# Sheet1.net
KiCad netlist of a schematic drawn in Altium Designer
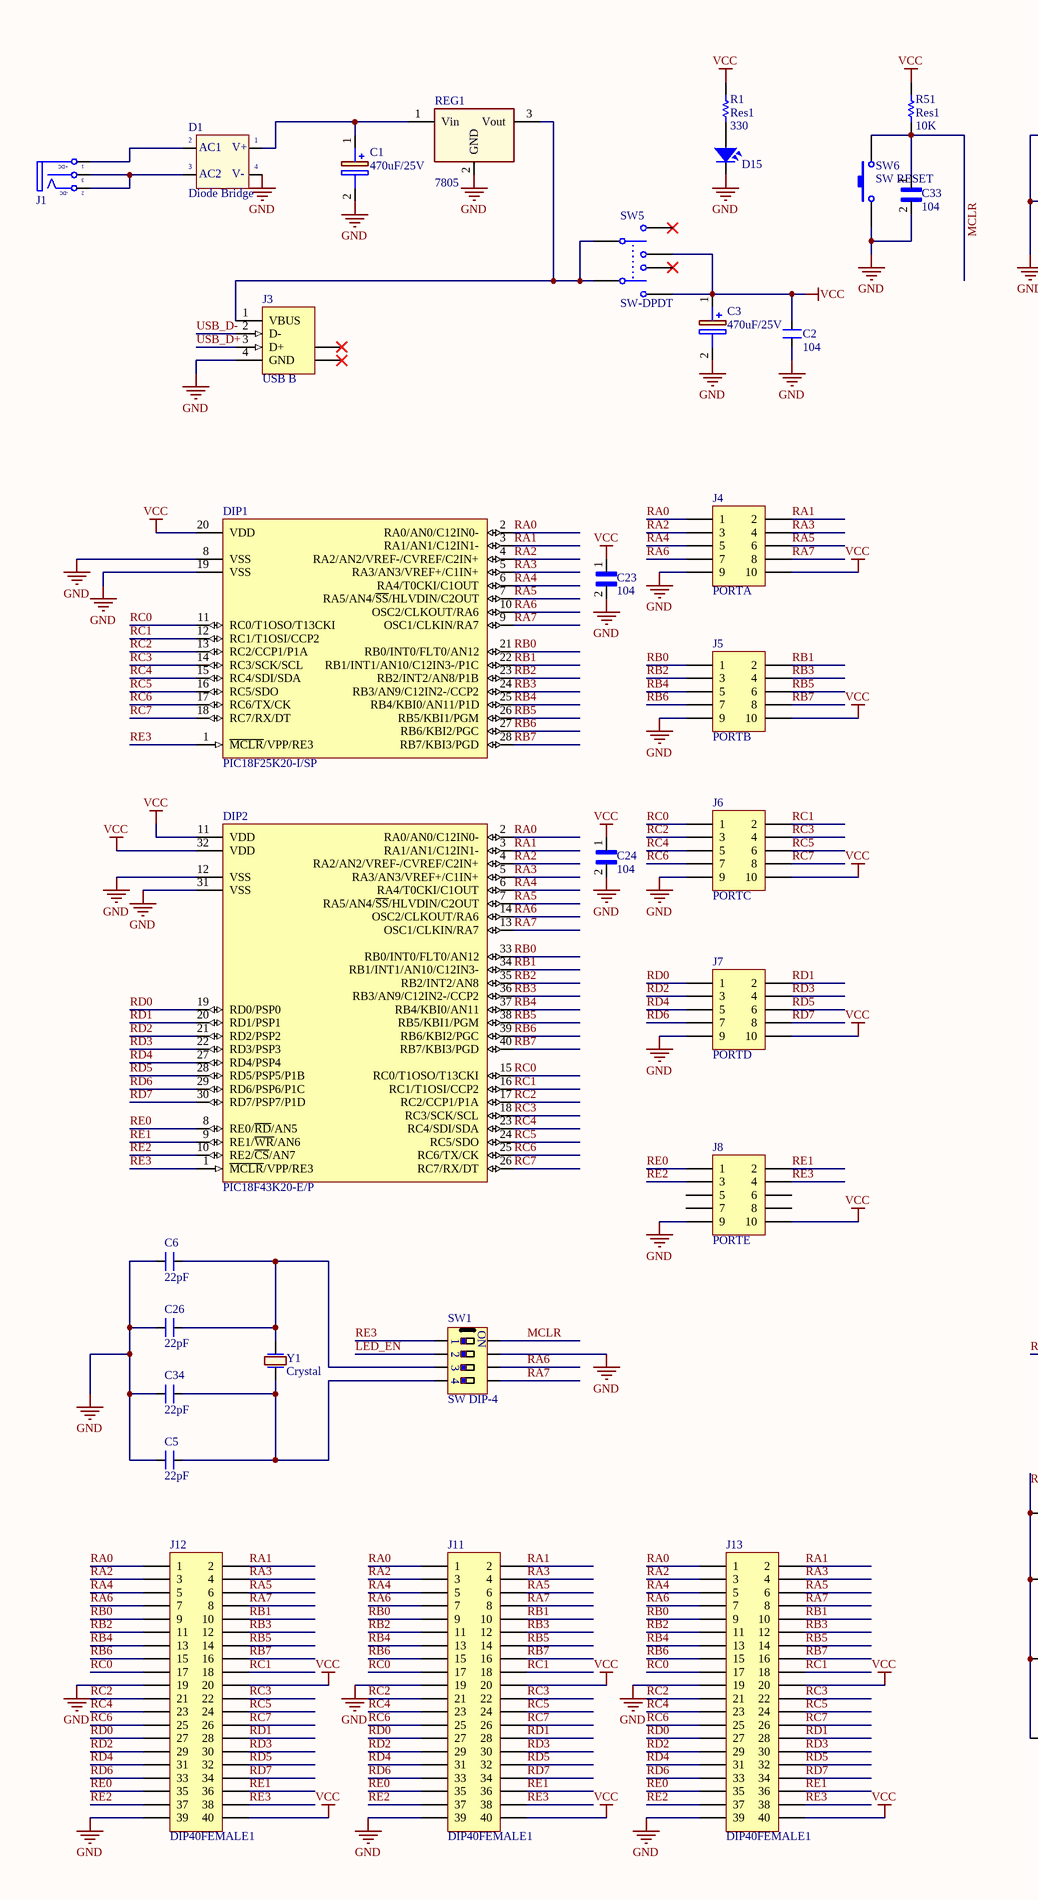
[diagram p0: Sheet1.SchDoc, left]
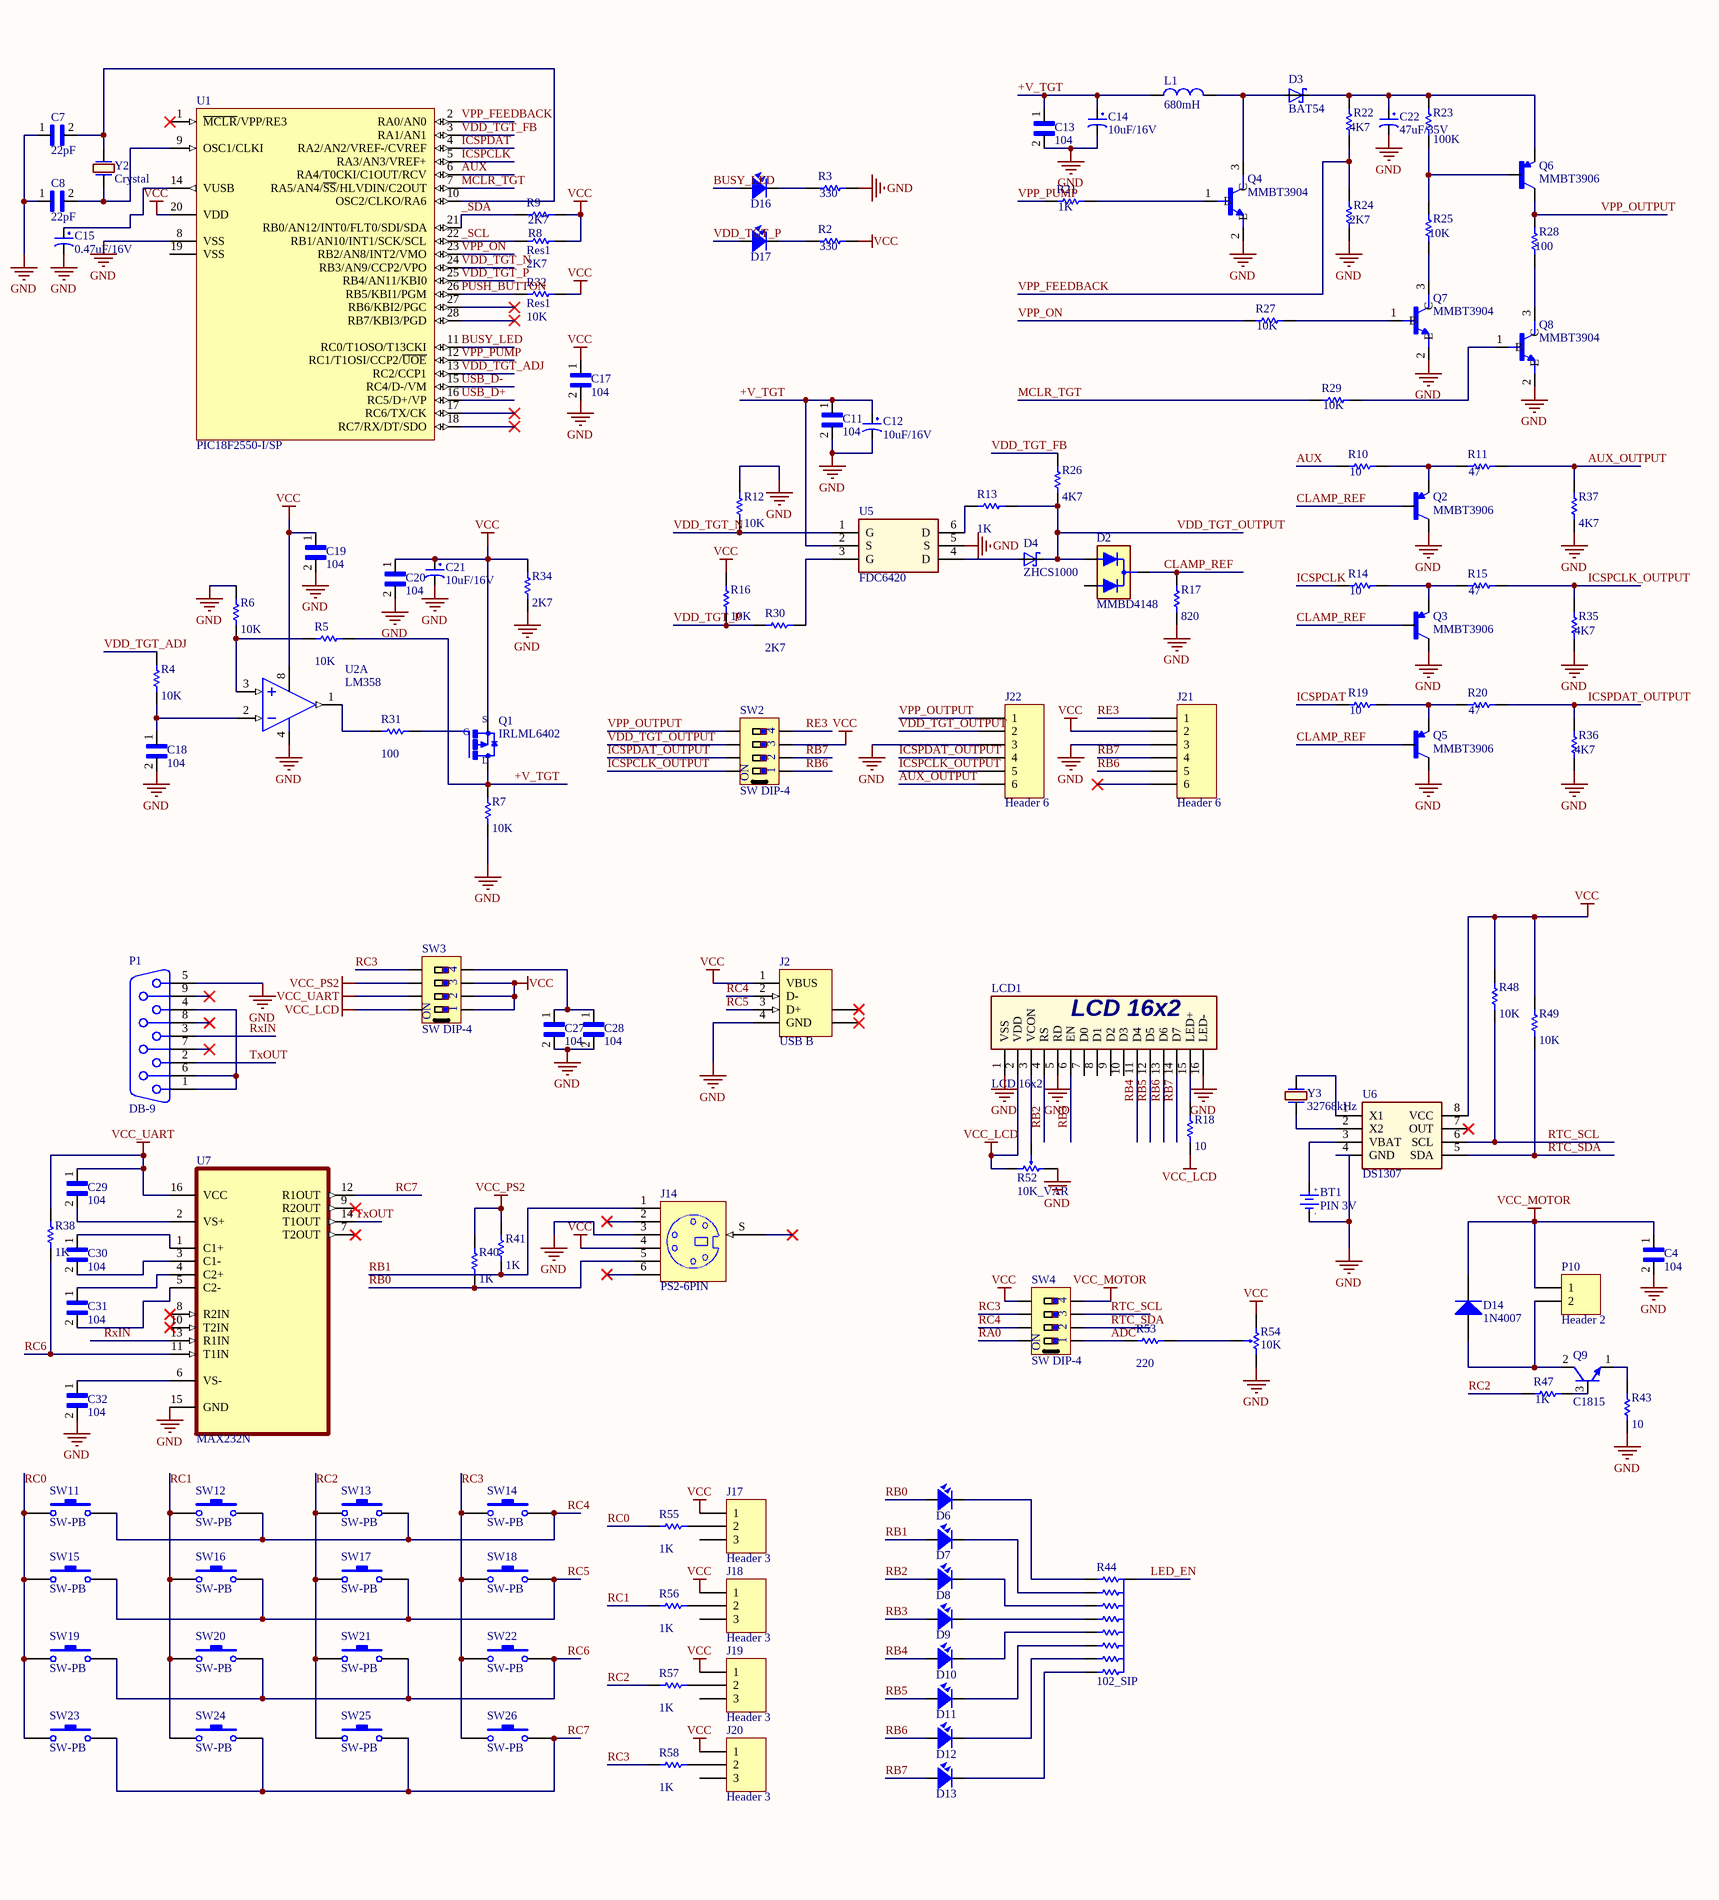
[diagram p1: Sheet1.SchDoc, right]

(export (version "E")
  (design (tool "Eeschema 10.0.6"))
  (components
    (comp (ref "BT1")
      (value "PIN 3V")
      (footprint "PIN3V")
      (description "Battery 3VDC")
      (libsource (lib "syhaunguyen") (part "PIN 3V"))
    )
    (comp (ref "C1")
      (value "470uF/25V")
      (footprint "SamacSys:CAPPRD500W60D1000H1400")
      (description "Capacitor Polarised")
      (fields
        (field (name "MANUFACTURER_PART_NUMBER") "ESL477M025AH9AA")
        (field (name "MOUSER PART NUMBER") "80-ESL477M025AH9AA")
      )
      (libsource (lib "SamacSys") (part "ESL477M025AH9AA"))
    )
    (comp (ref "C2")
      (value "104")
      (footprint "CN2")
      (description "Cap np 104 => 105pF")
      (libsource (lib "syhaunguyen") (part "CN2"))
    )
    (comp (ref "C3")
      (value "470uF/25V")
      (footprint "SamacSys:CAPPRD500W60D1000H1400")
      (description "Capacitor Polarised")
      (fields
        (field (name "MANUFACTURER_PART_NUMBER") "ESL477M025AH9AA")
        (field (name "MOUSER PART NUMBER") "80-ESL477M025AH9AA")
      )
      (libsource (lib "SamacSys") (part "ESL477M025AH9AA"))
    )
    (comp (ref "C4")
      (value "104")
      (footprint "CAPC1608X90")
      (description "0.1ÂµF Â±10% 50V Ceramic Capacitor X7R 0603 _1608 Metric_")
      (fields (field (name "DIGI-KEY_PART_NUMBER") "311-1344-1-ND") (field (name "MP") "CC0603KRX7R9BB104"))
      (libsource (lib "CC0603KRX7R9BB104") (part "CC0603KRX7R9BB104"))
    )
    (comp (ref "C5")
      (value "22pF")
      (footprint "CN2")
      (description "Cap np 104 => 105pF")
      (libsource (lib "syhaunguyen") (part "CN2"))
    )
    (comp (ref "C6")
      (value "22pF")
      (footprint "CN2")
      (description "Cap np 104 => 105pF")
      (libsource (lib "syhaunguyen") (part "CN2"))
    )
    (comp (ref "C7")
      (value "22pF")
      (footprint "CAPC1608X90")
      (description "0.1ÂµF Â±10% 50V Ceramic Capacitor X7R 0603 _1608 Metric_")
      (fields (field (name "DIGI-KEY_PART_NUMBER") "311-1344-1-ND") (field (name "MP") "CC0603KRX7R9BB104"))
      (libsource (lib "") (part "CC0603KRX7R9BB104_1"))
    )
    (comp (ref "C8")
      (value "22pF")
      (footprint "CAPC1608X90")
      (description "0.1ÂµF Â±10% 50V Ceramic Capacitor X7R 0603 _1608 Metric_")
      (fields (field (name "DIGI-KEY_PART_NUMBER") "311-1344-1-ND") (field (name "MP") "CC0603KRX7R9BB104"))
      (libsource (lib "") (part "CC0603KRX7R9BB104_1"))
    )
    (comp (ref "C11")
      (value "104")
      (footprint "CAPC1608X90")
      (description "0.1ÂµF Â±10% 50V Ceramic Capacitor X7R 0603 _1608 Metric_")
      (fields (field (name "DIGI-KEY_PART_NUMBER") "311-1344-1-ND") (field (name "MP") "CC0603KRX7R9BB104"))
      (libsource (lib "CC0603KRX7R9BB104") (part "CC0603KRX7R9BB104"))
    )
    (comp (ref "C12")
      (value "10uF/16V")
      (footprint "CP1/2")
      (description "Cap P  0,1uF < 22uF , 16 - 50V")
      (libsource (lib "syhaunguyen") (part "CP1"))
    )
    (comp (ref "C13")
      (value "104")
      (footprint "CAPC1608X90")
      (description "0.1ÂµF Â±10% 50V Ceramic Capacitor X7R 0603 _1608 Metric_")
      (fields (field (name "DIGI-KEY_PART_NUMBER") "311-1344-1-ND") (field (name "MP") "CC0603KRX7R9BB104"))
      (libsource (lib "CC0603KRX7R9BB104") (part "CC0603KRX7R9BB104"))
    )
    (comp (ref "C14")
      (value "10uF/16V")
      (footprint "CP1/2")
      (description "Cap P  0,1uF < 22uF , 16 - 50V")
      (libsource (lib "syhaunguyen") (part "CP1"))
    )
    (comp (ref "C15")
      (value "0.47uF/16V")
      (footprint "CP1/2")
      (description "Cap P  0,1uF < 22uF , 16 - 50V")
      (libsource (lib "syhaunguyen") (part "CP1"))
    )
    (comp (ref "C17")
      (value "104")
      (footprint "CAPC1608X90")
      (description "0.1ÂµF Â±10% 50V Ceramic Capacitor X7R 0603 _1608 Metric_")
      (fields (field (name "DIGI-KEY_PART_NUMBER") "311-1344-1-ND") (field (name "MP") "CC0603KRX7R9BB104"))
      (libsource (lib "CC0603KRX7R9BB104") (part "CC0603KRX7R9BB104"))
    )
    (comp (ref "C18")
      (value "104")
      (footprint "CAPC1608X90")
      (description "0.1ÂµF Â±10% 50V Ceramic Capacitor X7R 0603 _1608 Metric_")
      (fields (field (name "DIGI-KEY_PART_NUMBER") "311-1344-1-ND") (field (name "MP") "CC0603KRX7R9BB104"))
      (libsource (lib "CC0603KRX7R9BB104") (part "CC0603KRX7R9BB104"))
    )
    (comp (ref "C19")
      (value "104")
      (footprint "CAPC1608X90")
      (description "0.1ÂµF Â±10% 50V Ceramic Capacitor X7R 0603 _1608 Metric_")
      (fields (field (name "DIGI-KEY_PART_NUMBER") "311-1344-1-ND") (field (name "MP") "CC0603KRX7R9BB104"))
      (libsource (lib "CC0603KRX7R9BB104") (part "CC0603KRX7R9BB104"))
    )
    (comp (ref "C20")
      (value "104")
      (footprint "CAPC1608X90")
      (description "0.1ÂµF Â±10% 50V Ceramic Capacitor X7R 0603 _1608 Metric_")
      (fields (field (name "DIGI-KEY_PART_NUMBER") "311-1344-1-ND") (field (name "MP") "CC0603KRX7R9BB104"))
      (libsource (lib "CC0603KRX7R9BB104") (part "CC0603KRX7R9BB104"))
    )
    (comp (ref "C21")
      (value "10uF/16V")
      (footprint "CP1/2")
      (description "Cap P  0,1uF < 22uF , 16 - 50V")
      (libsource (lib "syhaunguyen") (part "CP1"))
    )
    (comp (ref "C22")
      (value "47uF/35V")
      (footprint "CP1/2")
      (description "Cap P  0,1uF < 22uF , 16 - 50V")
      (libsource (lib "syhaunguyen") (part "CP1"))
    )
    (comp (ref "C23")
      (value "104")
      (footprint "CAPC1608X90")
      (description "0.1ÂµF Â±10% 50V Ceramic Capacitor X7R 0603 _1608 Metric_")
      (fields (field (name "DIGI-KEY_PART_NUMBER") "311-1344-1-ND") (field (name "MP") "CC0603KRX7R9BB104"))
      (libsource (lib "CC0603KRX7R9BB104") (part "CC0603KRX7R9BB104"))
    )
    (comp (ref "C24")
      (value "104")
      (footprint "CAPC1608X90")
      (description "0.1ÂµF Â±10% 50V Ceramic Capacitor X7R 0603 _1608 Metric_")
      (fields (field (name "DIGI-KEY_PART_NUMBER") "311-1344-1-ND") (field (name "MP") "CC0603KRX7R9BB104"))
      (libsource (lib "CC0603KRX7R9BB104") (part "CC0603KRX7R9BB104"))
    )
    (comp (ref "C26")
      (value "22pF")
      (footprint "CN2")
      (description "Cap np 104 => 105pF")
      (libsource (lib "syhaunguyen") (part "CN2"))
    )
    (comp (ref "C27")
      (value "104")
      (footprint "CAPC1608X90")
      (description "0.1ÂµF Â±10% 50V Ceramic Capacitor X7R 0603 _1608 Metric_")
      (fields (field (name "DIGI-KEY_PART_NUMBER") "311-1344-1-ND") (field (name "MP") "CC0603KRX7R9BB104"))
      (libsource (lib "CC0603KRX7R9BB104") (part "CC0603KRX7R9BB104"))
    )
    (comp (ref "C28")
      (value "104")
      (footprint "CAPC1608X90")
      (description "0.1ÂµF Â±10% 50V Ceramic Capacitor X7R 0603 _1608 Metric_")
      (fields (field (name "DIGI-KEY_PART_NUMBER") "311-1344-1-ND") (field (name "MP") "CC0603KRX7R9BB104"))
      (libsource (lib "CC0603KRX7R9BB104") (part "CC0603KRX7R9BB104"))
    )
    (comp (ref "C29")
      (value "104")
      (footprint "CAPC1608X90")
      (description "0.1ÂµF Â±10% 50V Ceramic Capacitor X7R 0603 _1608 Metric_")
      (fields (field (name "DIGI-KEY_PART_NUMBER") "311-1344-1-ND") (field (name "MP") "CC0603KRX7R9BB104"))
      (libsource (lib "CC0603KRX7R9BB104") (part "CC0603KRX7R9BB104"))
    )
    (comp (ref "C30")
      (value "104")
      (footprint "CAPC1608X90")
      (description "0.1ÂµF Â±10% 50V Ceramic Capacitor X7R 0603 _1608 Metric_")
      (fields (field (name "DIGI-KEY_PART_NUMBER") "311-1344-1-ND") (field (name "MP") "CC0603KRX7R9BB104"))
      (libsource (lib "CC0603KRX7R9BB104") (part "CC0603KRX7R9BB104"))
    )
    (comp (ref "C31")
      (value "104")
      (footprint "CAPC1608X90")
      (description "0.1ÂµF Â±10% 50V Ceramic Capacitor X7R 0603 _1608 Metric_")
      (fields (field (name "DIGI-KEY_PART_NUMBER") "311-1344-1-ND") (field (name "MP") "CC0603KRX7R9BB104"))
      (libsource (lib "CC0603KRX7R9BB104") (part "CC0603KRX7R9BB104"))
    )
    (comp (ref "C32")
      (value "104")
      (footprint "CAPC1608X90")
      (description "0.1ÂµF Â±10% 50V Ceramic Capacitor X7R 0603 _1608 Metric_")
      (fields (field (name "DIGI-KEY_PART_NUMBER") "311-1344-1-ND") (field (name "MP") "CC0603KRX7R9BB104"))
      (libsource (lib "CC0603KRX7R9BB104") (part "CC0603KRX7R9BB104"))
    )
    (comp (ref "C33")
      (value "104")
      (footprint "CAPC1608X90")
      (description "0.1ÂµF Â±10% 50V Ceramic Capacitor X7R 0603 _1608 Metric_")
      (fields (field (name "DIGI-KEY_PART_NUMBER") "311-1344-1-ND") (field (name "MP") "CC0603KRX7R9BB104"))
      (libsource (lib "CC0603KRX7R9BB104") (part "CC0603KRX7R9BB104"))
    )
    (comp (ref "C34")
      (value "22pF")
      (footprint "CN2")
      (description "Cap np 104 => 105pF")
      (libsource (lib "syhaunguyen") (part "CN2"))
    )
    (comp (ref "D1")
      (value "Diode Bridge")
      (footprint "BRIDGE DIODE 2A")
      (description "Convert AC to DC voltage, 4 pin")
      (libsource (lib "BKIT4U_LIB") (part "Diode Bridge"))
    )
    (comp (ref "D2")
      (value "MMBD4148")
      (footprint "SOT23")
      (description "Diode Array 1 Pair Series Connection Standard 100V 200mA Surface Mount TO-236-3, SC-59, SOT-23-3")
      (fields (field (name "MF") "ON Semiconductor"))
      (libsource (lib "MMBD4148") (part "MMBD4148"))
    )
    (comp (ref "D3")
      (value "BAT54")
      (footprint "SOT23")
      (description "Diode Schottky 30V 200mA Surface Mount SOT-23-3 _TO-236_")
      (fields (field (name "MF") "ON Semiconductor"))
      (libsource (lib "BAT54") (part "BAT54"))
    )
    (comp (ref "D4")
      (value "ZHCS1000")
      (footprint "SOT-23")
      (description "Diode Schottky 40V 1A _DC_ Surface Mount SOT-23-3")
      (fields (field (name "MF") "Diodes Inc."))
      (libsource (lib "ZHCS1000") (part "ZHCS1000"))
    )
    (comp (ref "D6")
      (value "LED")
      (footprint "LED-3")
      (description "LED Single colour Green and Red")
      (libsource (lib "syhaunguyen") (part "LED"))
    )
    (comp (ref "D7")
      (value "LED")
      (footprint "LED-3")
      (description "LED Single colour Green and Red")
      (libsource (lib "syhaunguyen") (part "LED"))
    )
    (comp (ref "D8")
      (value "LED")
      (footprint "LED-3")
      (description "LED Single colour Green and Red")
      (libsource (lib "syhaunguyen") (part "LED"))
    )
    (comp (ref "D9")
      (value "LED")
      (footprint "LED-3")
      (description "LED Single colour Green and Red")
      (libsource (lib "syhaunguyen") (part "LED"))
    )
    (comp (ref "D10")
      (value "LED")
      (footprint "LED-3")
      (description "LED Single colour Green and Red")
      (libsource (lib "syhaunguyen") (part "LED"))
    )
    (comp (ref "D11")
      (value "LED")
      (footprint "LED-3")
      (description "LED Single colour Green and Red")
      (libsource (lib "syhaunguyen") (part "LED"))
    )
    (comp (ref "D12")
      (value "LED")
      (footprint "LED-3")
      (description "LED Single colour Green and Red")
      (libsource (lib "syhaunguyen") (part "LED"))
    )
    (comp (ref "D13")
      (value "LED")
      (footprint "LED-3")
      (description "LED Single colour Green and Red")
      (libsource (lib "syhaunguyen") (part "LED"))
    )
    (comp (ref "D14")
      (value "1N4007")
      (footprint "DO-41")
      (description "1 Amp General Purpose Rectifier")
      (fields (field (name "PUBLISHER") "Altium Limited"))
      (libsource (lib "Miscellaneous Devices") (part "Diode 1N4007"))
    )
    (comp (ref "D15")
      (value "LED")
      (footprint "LED-3")
      (description "LED Single colour Green and Red")
      (libsource (lib "syhaunguyen") (part "LED"))
    )
    (comp (ref "D16")
      (value "LED")
      (footprint "LED-3")
      (description "LED Single colour Green and Red")
      (libsource (lib "syhaunguyen") (part "LED"))
    )
    (comp (ref "D17")
      (value "LED")
      (footprint "LED-3")
      (description "LED Single colour Green and Red")
      (libsource (lib "syhaunguyen") (part "LED"))
    )
    (comp (ref "DIP1")
      (value "PIC18F25K20-I/SP")
      (footprint "SPDIP300-SP28")
      (fields (field (name "PUBLISHER") "Altium Limited"))
      (libsource (lib "Microchip Microcontroller 8-Bit PIC18") (part "PIC18F25K20-I/SP"))
    )
    (comp (ref "DIP2")
      (value "PIC18F43K20-E/P")
      (footprint "PDIP600-P40")
      (description "Flash Microcontroller with nanoWatt XLP Technology, 40-pin PDIP, Extended Temperature")
      (fields (field (name "PUBLISHER") "Altium Limited"))
      (libsource (lib "Microchip Microcontroller 8-Bit PIC18") (part "PIC18F43K20-E/P"))
    )
    (comp (ref "J1")
      (value "CON DC PWR")
      (footprint "CON PWR 5MM")
      (description "DC input connector")
      (libsource (lib "BKIT4U_LIB") (part "CON DC PWR"))
    )
    (comp (ref "J2")
      (value "USB B")
      (footprint "CON USB B")
      (description "USB type B, 4 pins")
      (libsource (lib "BKIT4U_LIB") (part "CON USB B"))
    )
    (comp (ref "J3")
      (value "USB B")
      (footprint "CON USB B")
      (description "USB type B, 4 pins")
      (libsource (lib "BKIT4U_LIB") (part "CON USB B"))
    )
    (comp (ref "J4")
      (value "PORTA")
      (footprint "HDR2X5")
      (description "Header, 5-Pin, Dual row")
      (fields (field (name "PUBLISHER") "Altium Limited"))
      (libsource (lib "Miscellaneous Connectors") (part "Header 5X2"))
    )
    (comp (ref "J5")
      (value "PORTB")
      (footprint "HDR2X5")
      (description "Header, 5-Pin, Dual row")
      (fields (field (name "PUBLISHER") "Altium Limited"))
      (libsource (lib "Miscellaneous Connectors") (part "Header 5X2"))
    )
    (comp (ref "J6")
      (value "PORTC")
      (footprint "HDR2X5")
      (description "Header, 5-Pin, Dual row")
      (fields (field (name "PUBLISHER") "Altium Limited"))
      (libsource (lib "Miscellaneous Connectors") (part "Header 5X2"))
    )
    (comp (ref "J7")
      (value "PORTD")
      (footprint "HDR2X5")
      (description "Header, 5-Pin, Dual row")
      (fields (field (name "PUBLISHER") "Altium Limited"))
      (libsource (lib "Miscellaneous Connectors") (part "Header 5X2"))
    )
    (comp (ref "J8")
      (value "PORTE")
      (footprint "HDR2X5")
      (description "Header, 5-Pin, Dual row")
      (fields (field (name "PUBLISHER") "Altium Limited"))
      (libsource (lib "Miscellaneous Connectors") (part "Header 5X2"))
    )
    (comp (ref "J11")
      (value "DIP40FEMALE1")
      (footprint "HDR2X20")
      (description "Header, 20-Pin, Dual row")
      (fields (field (name "PUBLISHER") "Altium Limited"))
      (libsource (lib "Miscellaneous Connectors") (part "Header 20X2"))
    )
    (comp (ref "J12")
      (value "DIP40FEMALE1")
      (footprint "HDR2X20")
      (description "Header, 20-Pin, Dual row")
      (fields (field (name "PUBLISHER") "Altium Limited"))
      (libsource (lib "Miscellaneous Connectors") (part "Header 20X2"))
    )
    (comp (ref "J13")
      (value "DIP40FEMALE1")
      (footprint "HDR2X20")
      (description "Header, 20-Pin, Dual row")
      (fields (field (name "PUBLISHER") "Altium Limited"))
      (libsource (lib "Miscellaneous Connectors") (part "Header 20X2"))
    )
    (comp (ref "J14")
      (value "PS2-6PIN")
      (footprint "PS2-6PIN")
      (description "6 Pin Through Hole PS2 Socket (Kycon P/N)")
      (fields (field (name "PUBLISHER") "Altium Limited"))
      (libsource (lib "Miscellaneous Connectors") (part "PS2-6PIN"))
    )
    (comp (ref "J17")
      (value "Header 3")
      (footprint "HDR1X3")
      (description "Header, 3-Pin")
      (fields (field (name "PUBLISHER") "Altium Limited"))
      (libsource (lib "Miscellaneous Connectors") (part "Header 3"))
    )
    (comp (ref "J18")
      (value "Header 3")
      (footprint "HDR1X3")
      (description "Header, 3-Pin")
      (fields (field (name "PUBLISHER") "Altium Limited"))
      (libsource (lib "Miscellaneous Connectors") (part "Header 3"))
    )
    (comp (ref "J19")
      (value "Header 3")
      (footprint "HDR1X3")
      (description "Header, 3-Pin")
      (fields (field (name "PUBLISHER") "Altium Limited"))
      (libsource (lib "Miscellaneous Connectors") (part "Header 3"))
    )
    (comp (ref "J20")
      (value "Header 3")
      (footprint "HDR1X3")
      (description "Header, 3-Pin")
      (fields (field (name "PUBLISHER") "Altium Limited"))
      (libsource (lib "Miscellaneous Connectors") (part "Header 3"))
    )
    (comp (ref "J21")
      (value "Header 6")
      (footprint "HDR1X6")
      (description "Header, 6-Pin")
      (fields (field (name "PUBLISHER") "Altium Limited"))
      (libsource (lib "Miscellaneous Connectors") (part "Header 6"))
    )
    (comp (ref "J22")
      (value "Header 6")
      (footprint "HDR1X6")
      (description "Header, 6-Pin")
      (fields (field (name "PUBLISHER") "Altium Limited"))
      (libsource (lib "Miscellaneous Connectors") (part "Header 6"))
    )
    (comp (ref "L1")
      (value "680mH")
      (footprint "L/0.4")
      (description "Inductor")
      (libsource (lib "syhaunguyen") (part "L1"))
    )
    (comp (ref "LCD1")
      (value "LCD 16x2")
      (footprint "LCD 16x2")
      (description "Character LCD 16x2")
      (libsource (lib "BKIT4U_LIB") (part "LCD 16x2"))
    )
    (comp (ref "P1")
      (value "DB-9")
      (footprint "CON DB9 FEMALE")
      (description "Connector D-Sub 9")
      (libsource (lib "BKIT4U_LIB") (part "CON DB-9"))
    )
    (comp (ref "P10")
      (value "Header 2")
      (footprint "HDR1X2")
      (description "Header, 2-Pin")
      (fields (field (name "PUBLISHER") "Altium Limited"))
      (libsource (lib "Miscellaneous Connectors") (part "Header 2"))
    )
    (comp (ref "Q1")
      (value "IRLML6402")
      (footprint "SOT23")
      (description "P-Channel 20V 3.7A _Ta_ 1.3W _Ta_ Surface Mount Micro3â„¢/SOT-23")
      (fields (field (name "MF") "Infineon Technologies"))
      (libsource (lib "IRLML6402") (part "IRLML6402"))
    )
    (comp (ref "Q2")
      (value "MMBT3906")
      (footprint "SOT23-3")
      (description "Bipolar _BJT_ Transistor")
      (fields (field (name "MF") "STMicroelectronics"))
      (libsource (lib "MMBT3906") (part "MMBT3906"))
    )
    (comp (ref "Q3")
      (value "MMBT3906")
      (footprint "SOT23-3")
      (description "Bipolar _BJT_ Transistor")
      (fields (field (name "MF") "STMicroelectronics"))
      (libsource (lib "MMBT3906") (part "MMBT3906"))
    )
    (comp (ref "Q4")
      (value "MMBT3904")
      (footprint "SOT95P240X120-3N")
      (description "Bipolar _BJT_ Transistor NPN 40V 200mA 270MHz 350mW Surface Mount SOT-23-3")
      (fields (field (name "MF") "STMicroelectronics"))
      (libsource (lib "MMBT3904") (part "MMBT3904"))
    )
    (comp (ref "Q5")
      (value "MMBT3906")
      (footprint "SOT23-3")
      (description "Bipolar _BJT_ Transistor")
      (fields (field (name "MF") "STMicroelectronics"))
      (libsource (lib "MMBT3906") (part "MMBT3906"))
    )
    (comp (ref "Q6")
      (value "MMBT3906")
      (footprint "SOT23-3")
      (description "Bipolar _BJT_ Transistor")
      (fields (field (name "MF") "STMicroelectronics"))
      (libsource (lib "MMBT3906") (part "MMBT3906"))
    )
    (comp (ref "Q7")
      (value "MMBT3904")
      (footprint "SOT95P240X120-3N")
      (description "Bipolar _BJT_ Transistor NPN 40V 200mA 270MHz 350mW Surface Mount SOT-23-3")
      (fields (field (name "MF") "STMicroelectronics"))
      (libsource (lib "MMBT3904") (part "MMBT3904"))
    )
    (comp (ref "Q8")
      (value "MMBT3904")
      (footprint "SOT95P240X120-3N")
      (description "Bipolar _BJT_ Transistor NPN 40V 200mA 270MHz 350mW Surface Mount SOT-23-3")
      (fields (field (name "MF") "STMicroelectronics"))
      (libsource (lib "MMBT3904") (part "MMBT3904"))
    )
    (comp (ref "Q9")
      (value "C1815")
      (footprint "BKIT4U_LIB:TO-92")
      (description "NPN Bipolar Transistor")
      (libsource (lib "BKIT4U_LIB") (part "Transistor NPN - C1815"))
    )
    (comp (ref "R1")
      (value "Res1")
      (footprint "AXIAL-0.3")
      (description "Resistor")
      (fields (field (name "ALTIUM_VALUE") "330") (field (name "PUBLISHER") "Altium Limited"))
      (libsource (lib "Miscellaneous Devices") (part "Res1"))
    )
    (comp (ref "R2")
      (value "330")
      (footprint "AXIAL-0.3")
      (description "Resistor")
      (fields (field (name "PUBLISHER") "Altium Limited"))
      (libsource (lib "Miscellaneous Devices") (part "Res1"))
    )
    (comp (ref "R3")
      (value "330")
      (footprint "AXIAL-0.3")
      (description "Resistor")
      (fields (field (name "PUBLISHER") "Altium Limited"))
      (libsource (lib "Miscellaneous Devices") (part "Res1"))
    )
    (comp (ref "R4")
      (value "10K")
      (footprint "AXIAL-0.3")
      (description "Resistor")
      (fields (field (name "PUBLISHER") "Altium Limited"))
      (libsource (lib "Miscellaneous Devices") (part "Res1"))
    )
    (comp (ref "R5")
      (value "10K")
      (footprint "AXIAL-0.3")
      (description "Resistor")
      (fields (field (name "PUBLISHER") "Altium Limited"))
      (libsource (lib "Miscellaneous Devices") (part "Res1"))
    )
    (comp (ref "R6")
      (value "10K")
      (footprint "AXIAL-0.3")
      (description "Resistor")
      (fields (field (name "PUBLISHER") "Altium Limited"))
      (libsource (lib "Miscellaneous Devices") (part "Res1"))
    )
    (comp (ref "R7")
      (value "10K")
      (footprint "AXIAL-0.3")
      (description "Resistor")
      (fields (field (name "PUBLISHER") "Altium Limited"))
      (libsource (lib "Miscellaneous Devices") (part "Res1"))
    )
    (comp (ref "R8")
      (value "Res1")
      (footprint "AXIAL-0.3")
      (description "Resistor")
      (fields (field (name "ALTIUM_VALUE") "2K7") (field (name "PUBLISHER") "Altium Limited"))
      (libsource (lib "Miscellaneous Devices") (part "Res1"))
    )
    (comp (ref "R9")
      (value "2K7")
      (footprint "AXIAL-0.3")
      (description "Resistor")
      (fields (field (name "PUBLISHER") "Altium Limited"))
      (libsource (lib "Miscellaneous Devices") (part "Res1"))
    )
    (comp (ref "R10")
      (value "10")
      (footprint "AXIAL-0.3")
      (description "Resistor")
      (fields (field (name "PUBLISHER") "Altium Limited"))
      (libsource (lib "Miscellaneous Devices") (part "Res1"))
    )
    (comp (ref "R11")
      (value "47")
      (footprint "AXIAL-0.3")
      (description "Resistor")
      (fields (field (name "PUBLISHER") "Altium Limited"))
      (libsource (lib "Miscellaneous Devices") (part "Res1"))
    )
    (comp (ref "R12")
      (value "10K")
      (footprint "AXIAL-0.3")
      (description "Resistor")
      (fields (field (name "PUBLISHER") "Altium Limited"))
      (libsource (lib "Miscellaneous Devices") (part "Res1"))
    )
    (comp (ref "R13")
      (value "1K")
      (footprint "AXIAL-0.3")
      (description "Resistor")
      (fields (field (name "PUBLISHER") "Altium Limited"))
      (libsource (lib "Miscellaneous Devices") (part "Res1"))
    )
    (comp (ref "R14")
      (value "10")
      (footprint "AXIAL-0.3")
      (description "Resistor")
      (fields (field (name "PUBLISHER") "Altium Limited"))
      (libsource (lib "Miscellaneous Devices") (part "Res1"))
    )
    (comp (ref "R15")
      (value "47")
      (footprint "AXIAL-0.3")
      (description "Resistor")
      (fields (field (name "PUBLISHER") "Altium Limited"))
      (libsource (lib "Miscellaneous Devices") (part "Res1"))
    )
    (comp (ref "R16")
      (value "10K")
      (footprint "AXIAL-0.3")
      (description "Resistor")
      (fields (field (name "PUBLISHER") "Altium Limited"))
      (libsource (lib "Miscellaneous Devices") (part "Res1"))
    )
    (comp (ref "R17")
      (value "820")
      (footprint "AXIAL-0.3")
      (description "Resistor")
      (fields (field (name "PUBLISHER") "Altium Limited"))
      (libsource (lib "Miscellaneous Devices") (part "Res1"))
    )
    (comp (ref "R18")
      (value "10")
      (footprint "AXIAL-0.3")
      (description "Resistor")
      (fields (field (name "PUBLISHER") "Altium Limited"))
      (libsource (lib "Miscellaneous Devices") (part "Res1"))
    )
    (comp (ref "R19")
      (value "10")
      (footprint "AXIAL-0.3")
      (description "Resistor")
      (fields (field (name "PUBLISHER") "Altium Limited"))
      (libsource (lib "Miscellaneous Devices") (part "Res1"))
    )
    (comp (ref "R20")
      (value "47")
      (footprint "AXIAL-0.3")
      (description "Resistor")
      (fields (field (name "PUBLISHER") "Altium Limited"))
      (libsource (lib "Miscellaneous Devices") (part "Res1"))
    )
    (comp (ref "R21")
      (value "1K")
      (footprint "AXIAL-0.3")
      (description "Resistor")
      (fields (field (name "PUBLISHER") "Altium Limited"))
      (libsource (lib "Miscellaneous Devices") (part "Res1"))
    )
    (comp (ref "R22")
      (value "4K7")
      (footprint "AXIAL-0.3")
      (description "Resistor")
      (fields (field (name "PUBLISHER") "Altium Limited"))
      (libsource (lib "Miscellaneous Devices") (part "Res1"))
    )
    (comp (ref "R23")
      (value "100K")
      (footprint "AXIAL-0.3")
      (description "Resistor")
      (fields (field (name "PUBLISHER") "Altium Limited"))
      (libsource (lib "Miscellaneous Devices") (part "Res1"))
    )
    (comp (ref "R24")
      (value "2K7")
      (footprint "AXIAL-0.3")
      (description "Resistor")
      (fields (field (name "PUBLISHER") "Altium Limited"))
      (libsource (lib "Miscellaneous Devices") (part "Res1"))
    )
    (comp (ref "R25")
      (value "10K")
      (footprint "AXIAL-0.3")
      (description "Resistor")
      (fields (field (name "PUBLISHER") "Altium Limited"))
      (libsource (lib "Miscellaneous Devices") (part "Res1"))
    )
    (comp (ref "R26")
      (value "4K7")
      (footprint "AXIAL-0.3")
      (description "Resistor")
      (fields (field (name "PUBLISHER") "Altium Limited"))
      (libsource (lib "Miscellaneous Devices") (part "Res1"))
    )
    (comp (ref "R27")
      (value "10K")
      (footprint "AXIAL-0.3")
      (description "Resistor")
      (fields (field (name "PUBLISHER") "Altium Limited"))
      (libsource (lib "Miscellaneous Devices") (part "Res1"))
    )
    (comp (ref "R28")
      (value "100")
      (footprint "AXIAL-0.3")
      (description "Resistor")
      (fields (field (name "PUBLISHER") "Altium Limited"))
      (libsource (lib "Miscellaneous Devices") (part "Res1"))
    )
    (comp (ref "R29")
      (value "10K")
      (footprint "AXIAL-0.3")
      (description "Resistor")
      (fields (field (name "PUBLISHER") "Altium Limited"))
      (libsource (lib "Miscellaneous Devices") (part "Res1"))
    )
    (comp (ref "R30")
      (value "2K7")
      (footprint "AXIAL-0.3")
      (description "Resistor")
      (fields (field (name "PUBLISHER") "Altium Limited"))
      (libsource (lib "Miscellaneous Devices") (part "Res1"))
    )
    (comp (ref "R31")
      (value "100")
      (footprint "AXIAL-0.3")
      (description "Resistor")
      (fields (field (name "PUBLISHER") "Altium Limited"))
      (libsource (lib "Miscellaneous Devices") (part "Res1"))
    )
    (comp (ref "R32")
      (value "Res1")
      (footprint "AXIAL-0.3")
      (description "Resistor")
      (fields (field (name "ALTIUM_VALUE") "10K") (field (name "PUBLISHER") "Altium Limited"))
      (libsource (lib "Miscellaneous Devices") (part "Res1"))
    )
    (comp (ref "R34")
      (value "2K7")
      (footprint "AXIAL-0.3")
      (description "Resistor")
      (fields (field (name "PUBLISHER") "Altium Limited"))
      (libsource (lib "Miscellaneous Devices") (part "Res1"))
    )
    (comp (ref "R35")
      (value "4K7")
      (footprint "AXIAL-0.3")
      (description "Resistor")
      (fields (field (name "PUBLISHER") "Altium Limited"))
      (libsource (lib "Miscellaneous Devices") (part "Res1"))
    )
    (comp (ref "R36")
      (value "4K7")
      (footprint "AXIAL-0.3")
      (description "Resistor")
      (fields (field (name "PUBLISHER") "Altium Limited"))
      (libsource (lib "Miscellaneous Devices") (part "Res1"))
    )
    (comp (ref "R37")
      (value "4K7")
      (footprint "AXIAL-0.3")
      (description "Resistor")
      (fields (field (name "PUBLISHER") "Altium Limited"))
      (libsource (lib "Miscellaneous Devices") (part "Res1"))
    )
    (comp (ref "R38")
      (value "1K")
      (footprint "AXIAL-0.3")
      (description "Resistor")
      (fields (field (name "PUBLISHER") "Altium Limited"))
      (libsource (lib "Miscellaneous Devices") (part "Res1"))
    )
    (comp (ref "R40")
      (value "1K")
      (footprint "AXIAL-0.3")
      (description "Resistor")
      (fields (field (name "PUBLISHER") "Altium Limited"))
      (libsource (lib "Miscellaneous Devices") (part "Res1"))
    )
    (comp (ref "R41")
      (value "1K")
      (footprint "AXIAL-0.3")
      (description "Resistor")
      (fields (field (name "PUBLISHER") "Altium Limited"))
      (libsource (lib "Miscellaneous Devices") (part "Res1"))
    )
    (comp (ref "R43")
      (value "10")
      (footprint "AXIAL-0.3")
      (description "Resistor")
      (fields (field (name "PUBLISHER") "Altium Limited"))
      (libsource (lib "Miscellaneous Devices") (part "Res1"))
    )
    (comp (ref "R44")
      (value "102_SIP")
      (footprint "R SIP9")
      (description "Resistor")
      (fields (field (name "PUBLISHER") "Altium Limited"))
      (libsource (lib "BKIT4U_LIB") (part "Resistor Sip9"))
    )
    (comp (ref "R47")
      (value "1K")
      (footprint "AXIAL-0.3")
      (description "Resistor")
      (fields (field (name "PUBLISHER") "Altium Limited"))
      (libsource (lib "Miscellaneous Devices") (part "Res1"))
    )
    (comp (ref "R48")
      (value "10K")
      (footprint "AXIAL-0.3")
      (description "Resistor")
      (fields (field (name "PUBLISHER") "Altium Limited"))
      (libsource (lib "Miscellaneous Devices") (part "Res1"))
    )
    (comp (ref "R49")
      (value "10K")
      (footprint "AXIAL-0.3")
      (description "Resistor")
      (fields (field (name "PUBLISHER") "Altium Limited"))
      (libsource (lib "Miscellaneous Devices") (part "Res1"))
    )
    (comp (ref "R51")
      (value "Res1")
      (footprint "AXIAL-0.3")
      (description "Resistor")
      (fields (field (name "ALTIUM_VALUE") "10K") (field (name "PUBLISHER") "Altium Limited"))
      (libsource (lib "Miscellaneous Devices") (part "Res1"))
    )
    (comp (ref "R52")
      (value "10K_VAR")
      (footprint "R VAR D")
      (description "Resistor Variable")
      (libsource (lib "BKIT4U_LIB") (part "Resistor Variable"))
    )
    (comp (ref "R53")
      (value "220")
      (footprint "AXIAL-0.3")
      (description "Resistor")
      (fields (field (name "PUBLISHER") "Altium Limited"))
      (libsource (lib "Miscellaneous Devices") (part "Res1"))
    )
    (comp (ref "R54")
      (value "10K")
      (footprint "R VAR B")
      (description "Resistor Variable")
      (libsource (lib "BKIT4U_LIB") (part "Resistor Variable"))
    )
    (comp (ref "R55")
      (value "1K")
      (footprint "AXIAL-0.3")
      (description "Resistor")
      (fields (field (name "PUBLISHER") "Altium Limited"))
      (libsource (lib "Miscellaneous Devices") (part "Res1"))
    )
    (comp (ref "R56")
      (value "1K")
      (footprint "AXIAL-0.3")
      (description "Resistor")
      (fields (field (name "PUBLISHER") "Altium Limited"))
      (libsource (lib "Miscellaneous Devices") (part "Res1"))
    )
    (comp (ref "R57")
      (value "1K")
      (footprint "AXIAL-0.3")
      (description "Resistor")
      (fields (field (name "PUBLISHER") "Altium Limited"))
      (libsource (lib "Miscellaneous Devices") (part "Res1"))
    )
    (comp (ref "R58")
      (value "1K")
      (footprint "AXIAL-0.3")
      (description "Resistor")
      (fields (field (name "PUBLISHER") "Altium Limited"))
      (libsource (lib "Miscellaneous Devices") (part "Res1"))
    )
    (comp (ref "REG1")
      (value "7805")
      (footprint "TO-220")
      (description "LDO Fixed Voltage regulator")
      (libsource (lib "BKIT4U_LIB") (part "78xx/78Mxx"))
    )
    (comp (ref "SW1") (value "SW DIP-4") (footprint "SW/DIP4") (libsource (lib "") (part "SW DIP-4_1")))
    (comp (ref "SW2")
      (value "SW DIP-4")
      (footprint "SW/DIP4")
      (libsource (lib "BKIT4U_LIB") (part "SW DIP-4"))
    )
    (comp (ref "SW3")
      (value "SW DIP-4")
      (footprint "SW/DIP4")
      (libsource (lib "BKIT4U_LIB") (part "SW DIP-4"))
    )
    (comp (ref "SW4")
      (value "SW DIP-4")
      (footprint "SW/DIP4")
      (libsource (lib "BKIT4U_LIB") (part "SW DIP-4"))
    )
    (comp (ref "SW5")
      (value "SW-DPDT")
      (footprint "DPDT-6")
      (description "Double-Pole, Double-Throw Switch")
      (fields (field (name "PUBLISHER") "Altium Limited"))
      (libsource (lib "Miscellaneous Devices") (part "SW-DPDT"))
    )
    (comp (ref "SW6")
      (value "SW RESET")
      (footprint "SPST-2")
      (description "Switch")
      (fields (field (name "PUBLISHER") "Altium Limited"))
      (libsource (lib "Miscellaneous Devices") (part "SW-PB"))
    )
    (comp (ref "SW11")
      (value "SW-PB")
      (footprint "SPST-2")
      (description "Switch")
      (fields (field (name "PUBLISHER") "Altium Limited"))
      (libsource (lib "Miscellaneous Devices") (part "SW-PB"))
    )
    (comp (ref "SW12")
      (value "SW-PB")
      (footprint "SPST-2")
      (description "Switch")
      (fields (field (name "PUBLISHER") "Altium Limited"))
      (libsource (lib "Miscellaneous Devices") (part "SW-PB"))
    )
    (comp (ref "SW13")
      (value "SW-PB")
      (footprint "SPST-2")
      (description "Switch")
      (fields (field (name "PUBLISHER") "Altium Limited"))
      (libsource (lib "Miscellaneous Devices") (part "SW-PB"))
    )
    (comp (ref "SW14")
      (value "SW-PB")
      (footprint "SPST-2")
      (description "Switch")
      (fields (field (name "PUBLISHER") "Altium Limited"))
      (libsource (lib "Miscellaneous Devices") (part "SW-PB"))
    )
    (comp (ref "SW15")
      (value "SW-PB")
      (footprint "SPST-2")
      (description "Switch")
      (fields (field (name "PUBLISHER") "Altium Limited"))
      (libsource (lib "Miscellaneous Devices") (part "SW-PB"))
    )
    (comp (ref "SW16")
      (value "SW-PB")
      (footprint "SPST-2")
      (description "Switch")
      (fields (field (name "PUBLISHER") "Altium Limited"))
      (libsource (lib "Miscellaneous Devices") (part "SW-PB"))
    )
    (comp (ref "SW17")
      (value "SW-PB")
      (footprint "SPST-2")
      (description "Switch")
      (fields (field (name "PUBLISHER") "Altium Limited"))
      (libsource (lib "Miscellaneous Devices") (part "SW-PB"))
    )
    (comp (ref "SW18")
      (value "SW-PB")
      (footprint "SPST-2")
      (description "Switch")
      (fields (field (name "PUBLISHER") "Altium Limited"))
      (libsource (lib "Miscellaneous Devices") (part "SW-PB"))
    )
    (comp (ref "SW19")
      (value "SW-PB")
      (footprint "SPST-2")
      (description "Switch")
      (fields (field (name "PUBLISHER") "Altium Limited"))
      (libsource (lib "Miscellaneous Devices") (part "SW-PB"))
    )
    (comp (ref "SW20")
      (value "SW-PB")
      (footprint "SPST-2")
      (description "Switch")
      (fields (field (name "PUBLISHER") "Altium Limited"))
      (libsource (lib "Miscellaneous Devices") (part "SW-PB"))
    )
    (comp (ref "SW21")
      (value "SW-PB")
      (footprint "SPST-2")
      (description "Switch")
      (fields (field (name "PUBLISHER") "Altium Limited"))
      (libsource (lib "Miscellaneous Devices") (part "SW-PB"))
    )
    (comp (ref "SW22")
      (value "SW-PB")
      (footprint "SPST-2")
      (description "Switch")
      (fields (field (name "PUBLISHER") "Altium Limited"))
      (libsource (lib "Miscellaneous Devices") (part "SW-PB"))
    )
    (comp (ref "SW23")
      (value "SW-PB")
      (footprint "SPST-2")
      (description "Switch")
      (fields (field (name "PUBLISHER") "Altium Limited"))
      (libsource (lib "Miscellaneous Devices") (part "SW-PB"))
    )
    (comp (ref "SW24")
      (value "SW-PB")
      (footprint "SPST-2")
      (description "Switch")
      (fields (field (name "PUBLISHER") "Altium Limited"))
      (libsource (lib "Miscellaneous Devices") (part "SW-PB"))
    )
    (comp (ref "SW25")
      (value "SW-PB")
      (footprint "SPST-2")
      (description "Switch")
      (fields (field (name "PUBLISHER") "Altium Limited"))
      (libsource (lib "Miscellaneous Devices") (part "SW-PB"))
    )
    (comp (ref "SW26")
      (value "SW-PB")
      (footprint "SPST-2")
      (description "Switch")
      (fields (field (name "PUBLISHER") "Altium Limited"))
      (libsource (lib "Miscellaneous Devices") (part "SW-PB"))
    )
    (comp (ref "U1")
      (value "PIC18F2550-I/SP")
      (footprint "SPDIP300-SP28")
      (fields (field (name "PUBLISHER") "Altium Limited"))
      (libsource (lib "Microchip Microcontroller 8-Bit PIC18") (part "PIC18F2550-I/SP"))
    )
    (comp (ref "U2")
      (value "LM358")
      (footprint "DIP8/W0.3")
      (description "Low-Power Dual Operational Amplifier")
      (libsource (lib "syhaunguyen") (part "LM358"))
    )
    (comp (ref "U5")
      (value "FDC6420")
      (footprint "SOT-6")
      (description "20V N & P-Channel PowerTrenchÒ MOSFETs")
      (libsource (lib "BKIT4U_LIB") (part "FDC6420"))
    )
    (comp (ref "U6") (value "DS1307") (footprint "DIP 8") (libsource (lib "BKIT4U_LIB") (part "DS1307")))
    (comp (ref "U7")
      (value "MAX232N")
      (footprint "DIP254P762X508-16")
      (description "2/2 Transceiver Full RS232 16-PDIP")
      (fields (field (name "MF") "Texas Instruments"))
      (libsource (lib "MAX232N") (part "MAX232N"))
    )
    (comp (ref "Y1")
      (value "Crystal")
      (footprint "Crystal HC49S DIP")
      (libsource (lib "") (part "Crystal_1"))
    )
    (comp (ref "Y2")
      (value "Crystal")
      (footprint "Crystal HC49S DIP")
      (libsource (lib "BKIT4U_LIB") (part "Crystal"))
    )
    (comp (ref "Y3") (value "32768kHz") (footprint "Crystal DIP-2") (libsource (lib "") (part "Crystal_1")))
  )
  (nets
    (net (code "1") (name "/+V_TGT") (class "Default")
      (node (ref "C11") (pin "1") (pinfunction "1_1") (pintype "passive"))
      (node (ref "C12") (pin "1") (pinfunction "1_1") (pintype "passive"))
      (node (ref "C13") (pin "1") (pinfunction "1_1") (pintype "passive"))
      (node (ref "C14") (pin "1") (pinfunction "1_1") (pintype "passive"))
      (node (ref "L1") (pin "1") (pinfunction "1_1") (pintype "passive"))
      (node (ref "Q1") (pin "3") (pinfunction "D_3") (pintype "passive"))
      (node (ref "R5") (pin "2") (pinfunction "2_2") (pintype "passive"))
      (node (ref "R7") (pin "2") (pinfunction "2_2") (pintype "passive"))
      (node (ref "U5") (pin "2") (pinfunction "S_2") (pintype "passive"))
    )
    (net (code "2") (name "/ADC") (class "Default")
      (node (ref "R53") (pin "1") (pinfunction "1_1") (pintype "passive"))
      (node (ref "SW4") (pin "1") (pinfunction "1_1") (pintype "passive"))
    )
    (net (code "3") (name "/AUX") (class "Default")
      (node (ref "R10") (pin "1") (pinfunction "1_1") (pintype "passive"))
      (node (ref "U1") (pin "6") (pinfunction "RA4/T0CKI/C1OUT/RCV_6") (pintype "bidirectional"))
    )
    (net (code "4") (name "/AUX_OUTPUT") (class "Default")
      (node (ref "J22") (pin "6") (pinfunction "6_6") (pintype "passive"))
      (node (ref "R11") (pin "2") (pinfunction "2_2") (pintype "passive"))
      (node (ref "R37") (pin "2") (pinfunction "2_2") (pintype "passive"))
    )
    (net (code "5") (name "/BUSY_LED") (class "Default")
      (node (ref "D16") (pin "1") (pinfunction "1_1") (pintype "passive"))
      (node (ref "U1") (pin "11") (pinfunction "RC0/T1OSO/T13CKI_11") (pintype "bidirectional"))
    )
    (net (code "6") (name "/CLAMP_REF") (class "Default")
      (node (ref "D2") (pin "3") (pinfunction "C_3") (pintype "passive"))
      (node (ref "Q2") (pin "1") (pinfunction "B_1") (pintype "passive"))
      (node (ref "Q3") (pin "1") (pinfunction "B_1") (pintype "passive"))
      (node (ref "Q5") (pin "1") (pinfunction "B_1") (pintype "passive"))
      (node (ref "R17") (pin "2") (pinfunction "2_2") (pintype "passive"))
    )
    (net (code "7") (name "/ICSPCLK") (class "Default")
      (node (ref "R14") (pin "1") (pinfunction "1_1") (pintype "passive"))
      (node (ref "U1") (pin "5") (pinfunction "RA3/AN3/VREF+_5") (pintype "bidirectional"))
    )
    (net (code "8") (name "/ICSPCLK_OUTPUT") (class "Default")
      (node (ref "J22") (pin "5") (pinfunction "5_5") (pintype "passive"))
      (node (ref "R15") (pin "2") (pinfunction "2_2") (pintype "passive"))
      (node (ref "R35") (pin "2") (pinfunction "2_2") (pintype "passive"))
      (node (ref "SW2") (pin "8") (pinfunction "8_8") (pintype "passive"))
    )
    (net (code "9") (name "/ICSPDAT") (class "Default")
      (node (ref "R19") (pin "1") (pinfunction "1_1") (pintype "passive"))
      (node (ref "U1") (pin "4") (pinfunction "RA2/AN2/VREF-/CVREF_4") (pintype "bidirectional"))
    )
    (net (code "10") (name "/ICSPDAT_OUTPUT") (class "Default")
      (node (ref "J22") (pin "4") (pinfunction "4_4") (pintype "passive"))
      (node (ref "R20") (pin "2") (pinfunction "2_2") (pintype "passive"))
      (node (ref "R36") (pin "2") (pinfunction "2_2") (pintype "passive"))
      (node (ref "SW2") (pin "7") (pinfunction "7_7") (pintype "passive"))
    )
    (net (code "11") (name "/LED_EN") (class "Default")
      (node (ref "R44") (pin "1") (pinfunction "1_1") (pintype "passive"))
      (node (ref "SW1") (pin "2") (pinfunction "2_2") (pintype "passive"))
    )
    (net (code "12") (name "/MCLR") (class "Default")
      (node (ref "C33") (pin "1") (pinfunction "1_1") (pintype "passive"))
      (node (ref "R51") (pin "1") (pinfunction "1_1") (pintype "passive"))
      (node (ref "SW1") (pin "8") (pinfunction "8_8") (pintype "passive"))
      (node (ref "SW6") (pin "2") (pinfunction "2_2") (pintype "passive"))
    )
    (net (code "13") (name "/MCLR_TGT") (class "Default")
      (node (ref "R29") (pin "1") (pinfunction "1_1") (pintype "passive"))
      (node (ref "U1") (pin "7") (pinfunction "RA5/AN4/~{SS}/HLVDIN/C2OUT_7") (pintype "bidirectional"))
    )
    (net (code "14") (name "/PUSH_BUTTON") (class "Default")
      (node (ref "R32") (pin "1") (pinfunction "1_1") (pintype "passive"))
      (node (ref "U1") (pin "26") (pinfunction "RB5/KBI1/PGM_26") (pintype "bidirectional"))
    )
    (net (code "15") (name "/RA0") (class "Default")
      (node (ref "DIP1") (pin "2") (pinfunction "RA0/AN0/C12IN0-_2") (pintype "bidirectional"))
      (node (ref "DIP2") (pin "2") (pinfunction "RA0/AN0/C12IN0-_2") (pintype "bidirectional"))
      (node (ref "J11") (pin "1") (pinfunction "1_1") (pintype "passive"))
      (node (ref "J12") (pin "1") (pinfunction "1_1") (pintype "passive"))
      (node (ref "J13") (pin "1") (pinfunction "1_1") (pintype "passive"))
      (node (ref "J4") (pin "1") (pinfunction "1_1") (pintype "passive"))
      (node (ref "SW4") (pin "8") (pinfunction "8_8") (pintype "passive"))
    )
    (net (code "16") (name "/RA1") (class "Default")
      (node (ref "DIP1") (pin "3") (pinfunction "RA1/AN1/C12IN1-_3") (pintype "bidirectional"))
      (node (ref "DIP2") (pin "3") (pinfunction "RA1/AN1/C12IN1-_3") (pintype "bidirectional"))
      (node (ref "J11") (pin "2") (pinfunction "2_2") (pintype "passive"))
      (node (ref "J12") (pin "2") (pinfunction "2_2") (pintype "passive"))
      (node (ref "J13") (pin "2") (pinfunction "2_2") (pintype "passive"))
      (node (ref "J4") (pin "2") (pinfunction "2_2") (pintype "passive"))
    )
    (net (code "17") (name "/RA2") (class "Default")
      (node (ref "DIP1") (pin "4") (pinfunction "RA2/AN2/VREF-/CVREF/C2IN+_4") (pintype "bidirectional"))
      (node (ref "DIP2") (pin "4") (pinfunction "RA2/AN2/VREF-/CVREF/C2IN+_4") (pintype "bidirectional"))
      (node (ref "J11") (pin "3") (pinfunction "3_3") (pintype "passive"))
      (node (ref "J12") (pin "3") (pinfunction "3_3") (pintype "passive"))
      (node (ref "J13") (pin "3") (pinfunction "3_3") (pintype "passive"))
      (node (ref "J4") (pin "3") (pinfunction "3_3") (pintype "passive"))
    )
    (net (code "18") (name "/RA3") (class "Default")
      (node (ref "DIP1") (pin "5") (pinfunction "RA3/AN3/VREF+/C1IN+_5") (pintype "bidirectional"))
      (node (ref "DIP2") (pin "5") (pinfunction "RA3/AN3/VREF+/C1IN+_5") (pintype "bidirectional"))
      (node (ref "J11") (pin "4") (pinfunction "4_4") (pintype "passive"))
      (node (ref "J12") (pin "4") (pinfunction "4_4") (pintype "passive"))
      (node (ref "J13") (pin "4") (pinfunction "4_4") (pintype "passive"))
      (node (ref "J4") (pin "4") (pinfunction "4_4") (pintype "passive"))
    )
    (net (code "19") (name "/RA4") (class "Default")
      (node (ref "DIP1") (pin "6") (pinfunction "RA4/T0CKI/C1OUT_6") (pintype "bidirectional"))
      (node (ref "DIP2") (pin "6") (pinfunction "RA4/T0CKI/C1OUT_6") (pintype "bidirectional"))
      (node (ref "J11") (pin "5") (pinfunction "5_5") (pintype "passive"))
      (node (ref "J12") (pin "5") (pinfunction "5_5") (pintype "passive"))
      (node (ref "J13") (pin "5") (pinfunction "5_5") (pintype "passive"))
      (node (ref "J4") (pin "5") (pinfunction "5_5") (pintype "passive"))
    )
    (net (code "20") (name "/RA5") (class "Default")
      (node (ref "DIP1") (pin "7") (pinfunction "RA5/AN4/~{SS}/HLVDIN/C2OUT_7") (pintype "bidirectional"))
      (node (ref "DIP2") (pin "7") (pinfunction "RA5/AN4/~{SS}/HLVDIN/C2OUT_7") (pintype "bidirectional"))
      (node (ref "J11") (pin "6") (pinfunction "6_6") (pintype "passive"))
      (node (ref "J12") (pin "6") (pinfunction "6_6") (pintype "passive"))
      (node (ref "J13") (pin "6") (pinfunction "6_6") (pintype "passive"))
      (node (ref "J4") (pin "6") (pinfunction "6_6") (pintype "passive"))
    )
    (net (code "21") (name "/RA6") (class "Default")
      (node (ref "DIP1") (pin "10") (pinfunction "OSC2/CLKOUT/RA6_10") (pintype "bidirectional"))
      (node (ref "DIP2") (pin "14") (pinfunction "OSC2/CLKOUT/RA6_14") (pintype "bidirectional"))
      (node (ref "J11") (pin "7") (pinfunction "7_7") (pintype "passive"))
      (node (ref "J12") (pin "7") (pinfunction "7_7") (pintype "passive"))
      (node (ref "J13") (pin "7") (pinfunction "7_7") (pintype "passive"))
      (node (ref "J4") (pin "7") (pinfunction "7_7") (pintype "passive"))
      (node (ref "SW1") (pin "6") (pinfunction "6_6") (pintype "passive"))
    )
    (net (code "22") (name "/RA7") (class "Default")
      (node (ref "DIP1") (pin "9") (pinfunction "OSC1/CLKIN/RA7_9") (pintype "bidirectional"))
      (node (ref "DIP2") (pin "13") (pinfunction "OSC1/CLKIN/RA7_13") (pintype "bidirectional"))
      (node (ref "J11") (pin "8") (pinfunction "8_8") (pintype "passive"))
      (node (ref "J12") (pin "8") (pinfunction "8_8") (pintype "passive"))
      (node (ref "J13") (pin "8") (pinfunction "8_8") (pintype "passive"))
      (node (ref "J4") (pin "8") (pinfunction "8_8") (pintype "passive"))
      (node (ref "SW1") (pin "5") (pinfunction "5_5") (pintype "passive"))
    )
    (net (code "23") (name "/RB0") (class "Default")
      (node (ref "D6") (pin "1") (pinfunction "1_1") (pintype "passive"))
      (node (ref "DIP1") (pin "21") (pinfunction "RB0/INT0/FLT0/AN12_21") (pintype "bidirectional"))
      (node (ref "DIP2") (pin "33") (pinfunction "RB0/INT0/FLT0/AN12_33") (pintype "bidirectional"))
      (node (ref "J11") (pin "9") (pinfunction "9_9") (pintype "passive"))
      (node (ref "J12") (pin "9") (pinfunction "9_9") (pintype "passive"))
      (node (ref "J13") (pin "9") (pinfunction "9_9") (pintype "passive"))
      (node (ref "J14") (pin "5") (pinfunction "5_5") (pintype "passive"))
      (node (ref "J5") (pin "1") (pinfunction "1_1") (pintype "passive"))
      (node (ref "R40") (pin "1") (pinfunction "1_1") (pintype "passive"))
    )
    (net (code "24") (name "/RB1") (class "Default")
      (node (ref "D7") (pin "1") (pinfunction "1_1") (pintype "passive"))
      (node (ref "DIP1") (pin "22") (pinfunction "RB1/INT1/AN10/C12IN3-/P1C_22") (pintype "bidirectional"))
      (node (ref "DIP2") (pin "34") (pinfunction "RB1/INT1/AN10/C12IN3-_34") (pintype "bidirectional"))
      (node (ref "J11") (pin "10") (pinfunction "10_10") (pintype "passive"))
      (node (ref "J12") (pin "10") (pinfunction "10_10") (pintype "passive"))
      (node (ref "J13") (pin "10") (pinfunction "10_10") (pintype "passive"))
      (node (ref "J14") (pin "1") (pinfunction "1_1") (pintype "passive"))
      (node (ref "J5") (pin "2") (pinfunction "2_2") (pintype "passive"))
      (node (ref "R41") (pin "1") (pinfunction "1_1") (pintype "passive"))
    )
    (net (code "25") (name "/RB2") (class "Default")
      (node (ref "D8") (pin "1") (pinfunction "1_1") (pintype "passive"))
      (node (ref "DIP1") (pin "23") (pinfunction "RB2/INT2/AN8/P1B_23") (pintype "bidirectional"))
      (node (ref "DIP2") (pin "35") (pinfunction "RB2/INT2/AN8_35") (pintype "bidirectional"))
      (node (ref "J11") (pin "11") (pinfunction "11_11") (pintype "passive"))
      (node (ref "J12") (pin "11") (pinfunction "11_11") (pintype "passive"))
      (node (ref "J13") (pin "11") (pinfunction "11_11") (pintype "passive"))
      (node (ref "J5") (pin "3") (pinfunction "3_3") (pintype "passive"))
      (node (ref "LCD1") (pin "4") (pinfunction "RS_4") (pintype "passive"))
    )
    (net (code "26") (name "/RB3") (class "Default")
      (node (ref "D9") (pin "1") (pinfunction "1_1") (pintype "passive"))
      (node (ref "DIP1") (pin "24") (pinfunction "RB3/AN9/C12IN2-/CCP2_24") (pintype "bidirectional"))
      (node (ref "DIP2") (pin "36") (pinfunction "RB3/AN9/C12IN2-/CCP2_36") (pintype "bidirectional"))
      (node (ref "J11") (pin "12") (pinfunction "12_12") (pintype "passive"))
      (node (ref "J12") (pin "12") (pinfunction "12_12") (pintype "passive"))
      (node (ref "J13") (pin "12") (pinfunction "12_12") (pintype "passive"))
      (node (ref "J5") (pin "4") (pinfunction "4_4") (pintype "passive"))
      (node (ref "LCD1") (pin "6") (pinfunction "EN_6") (pintype "passive"))
    )
    (net (code "27") (name "/RB4") (class "Default")
      (node (ref "D10") (pin "1") (pinfunction "1_1") (pintype "passive"))
      (node (ref "DIP1") (pin "25") (pinfunction "RB4/KBI0/AN11/P1D_25") (pintype "bidirectional"))
      (node (ref "DIP2") (pin "37") (pinfunction "RB4/KBI0/AN11_37") (pintype "bidirectional"))
      (node (ref "J11") (pin "13") (pinfunction "13_13") (pintype "passive"))
      (node (ref "J12") (pin "13") (pinfunction "13_13") (pintype "passive"))
      (node (ref "J13") (pin "13") (pinfunction "13_13") (pintype "passive"))
      (node (ref "J5") (pin "5") (pinfunction "5_5") (pintype "passive"))
      (node (ref "LCD1") (pin "11") (pinfunction "D4_11") (pintype "passive"))
    )
    (net (code "28") (name "/RB5") (class "Default")
      (node (ref "D11") (pin "1") (pinfunction "1_1") (pintype "passive"))
      (node (ref "DIP1") (pin "26") (pinfunction "RB5/KBI1/PGM_26") (pintype "bidirectional"))
      (node (ref "DIP2") (pin "38") (pinfunction "RB5/KBI1/PGM_38") (pintype "bidirectional"))
      (node (ref "J11") (pin "14") (pinfunction "14_14") (pintype "passive"))
      (node (ref "J12") (pin "14") (pinfunction "14_14") (pintype "passive"))
      (node (ref "J13") (pin "14") (pinfunction "14_14") (pintype "passive"))
      (node (ref "J5") (pin "6") (pinfunction "6_6") (pintype "passive"))
      (node (ref "LCD1") (pin "12") (pinfunction "D5_12") (pintype "passive"))
    )
    (net (code "29") (name "/RB6") (class "Default")
      (node (ref "D12") (pin "1") (pinfunction "1_1") (pintype "passive"))
      (node (ref "DIP1") (pin "27") (pinfunction "RB6/KBI2/PGC_27") (pintype "bidirectional"))
      (node (ref "DIP2") (pin "39") (pinfunction "RB6/KBI2/PGC_39") (pintype "bidirectional"))
      (node (ref "J11") (pin "15") (pinfunction "15_15") (pintype "passive"))
      (node (ref "J12") (pin "15") (pinfunction "15_15") (pintype "passive"))
      (node (ref "J13") (pin "15") (pinfunction "15_15") (pintype "passive"))
      (node (ref "J21") (pin "5") (pinfunction "5_5") (pintype "passive"))
      (node (ref "J5") (pin "7") (pinfunction "7_7") (pintype "passive"))
      (node (ref "LCD1") (pin "13") (pinfunction "D6_13") (pintype "passive"))
      (node (ref "SW2") (pin "1") (pinfunction "1_1") (pintype "passive"))
    )
    (net (code "30") (name "/RB7") (class "Default")
      (node (ref "D13") (pin "1") (pinfunction "1_1") (pintype "passive"))
      (node (ref "DIP1") (pin "28") (pinfunction "RB7/KBI3/PGD_28") (pintype "bidirectional"))
      (node (ref "DIP2") (pin "40") (pinfunction "RB7/KBI3/PGD_40") (pintype "bidirectional"))
      (node (ref "J11") (pin "16") (pinfunction "16_16") (pintype "passive"))
      (node (ref "J12") (pin "16") (pinfunction "16_16") (pintype "passive"))
      (node (ref "J13") (pin "16") (pinfunction "16_16") (pintype "passive"))
      (node (ref "J21") (pin "4") (pinfunction "4_4") (pintype "passive"))
      (node (ref "J5") (pin "8") (pinfunction "8_8") (pintype "passive"))
      (node (ref "LCD1") (pin "14") (pinfunction "D7_14") (pintype "passive"))
      (node (ref "SW2") (pin "2") (pinfunction "2_2") (pintype "passive"))
    )
    (net (code "31") (name "/RC0") (class "Default")
      (node (ref "DIP1") (pin "11") (pinfunction "RC0/T1OSO/T13CKI_11") (pintype "bidirectional"))
      (node (ref "DIP2") (pin "15") (pinfunction "RC0/T1OSO/T13CKI_15") (pintype "bidirectional"))
      (node (ref "J11") (pin "17") (pinfunction "17_17") (pintype "passive"))
      (node (ref "J12") (pin "17") (pinfunction "17_17") (pintype "passive"))
      (node (ref "J13") (pin "17") (pinfunction "17_17") (pintype "passive"))
      (node (ref "J6") (pin "1") (pinfunction "1_1") (pintype "passive"))
      (node (ref "R55") (pin "1") (pinfunction "1_1") (pintype "passive"))
      (node (ref "SW11") (pin "1") (pinfunction "1_1") (pintype "passive"))
      (node (ref "SW15") (pin "1") (pinfunction "1_1") (pintype "passive"))
      (node (ref "SW19") (pin "1") (pinfunction "1_1") (pintype "passive"))
      (node (ref "SW23") (pin "1") (pinfunction "1_1") (pintype "passive"))
    )
    (net (code "32") (name "/RC1") (class "Default")
      (node (ref "DIP1") (pin "12") (pinfunction "RC1/T1OSI/CCP2_12") (pintype "bidirectional"))
      (node (ref "DIP2") (pin "16") (pinfunction "RC1/T1OSI/CCP2_16") (pintype "bidirectional"))
      (node (ref "J11") (pin "18") (pinfunction "18_18") (pintype "passive"))
      (node (ref "J12") (pin "18") (pinfunction "18_18") (pintype "passive"))
      (node (ref "J13") (pin "18") (pinfunction "18_18") (pintype "passive"))
      (node (ref "J6") (pin "2") (pinfunction "2_2") (pintype "passive"))
      (node (ref "R56") (pin "1") (pinfunction "1_1") (pintype "passive"))
      (node (ref "SW12") (pin "1") (pinfunction "1_1") (pintype "passive"))
      (node (ref "SW16") (pin "1") (pinfunction "1_1") (pintype "passive"))
      (node (ref "SW20") (pin "1") (pinfunction "1_1") (pintype "passive"))
      (node (ref "SW24") (pin "1") (pinfunction "1_1") (pintype "passive"))
    )
    (net (code "33") (name "/RC2") (class "Default")
      (node (ref "DIP1") (pin "13") (pinfunction "RC2/CCP1/P1A_13") (pintype "bidirectional"))
      (node (ref "DIP2") (pin "17") (pinfunction "RC2/CCP1/P1A_17") (pintype "bidirectional"))
      (node (ref "J11") (pin "21") (pinfunction "21_21") (pintype "passive"))
      (node (ref "J12") (pin "21") (pinfunction "21_21") (pintype "passive"))
      (node (ref "J13") (pin "21") (pinfunction "21_21") (pintype "passive"))
      (node (ref "J6") (pin "3") (pinfunction "3_3") (pintype "passive"))
      (node (ref "R47") (pin "1") (pinfunction "1_1") (pintype "passive"))
      (node (ref "R57") (pin "1") (pinfunction "1_1") (pintype "passive"))
      (node (ref "SW13") (pin "1") (pinfunction "1_1") (pintype "passive"))
      (node (ref "SW17") (pin "1") (pinfunction "1_1") (pintype "passive"))
      (node (ref "SW21") (pin "1") (pinfunction "1_1") (pintype "passive"))
      (node (ref "SW25") (pin "1") (pinfunction "1_1") (pintype "passive"))
    )
    (net (code "34") (name "/RC3") (class "Default")
      (node (ref "DIP1") (pin "14") (pinfunction "RC3/SCK/SCL_14") (pintype "bidirectional"))
      (node (ref "DIP2") (pin "18") (pinfunction "RC3/SCK/SCL_18") (pintype "bidirectional"))
      (node (ref "J11") (pin "22") (pinfunction "22_22") (pintype "passive"))
      (node (ref "J12") (pin "22") (pinfunction "22_22") (pintype "passive"))
      (node (ref "J13") (pin "22") (pinfunction "22_22") (pintype "passive"))
      (node (ref "J6") (pin "4") (pinfunction "4_4") (pintype "passive"))
      (node (ref "R58") (pin "1") (pinfunction "1_1") (pintype "passive"))
      (node (ref "SW14") (pin "1") (pinfunction "1_1") (pintype "passive"))
      (node (ref "SW18") (pin "1") (pinfunction "1_1") (pintype "passive"))
      (node (ref "SW22") (pin "1") (pinfunction "1_1") (pintype "passive"))
      (node (ref "SW26") (pin "1") (pinfunction "1_1") (pintype "passive"))
      (node (ref "SW3") (pin "5") (pinfunction "5_5") (pintype "passive"))
      (node (ref "SW4") (pin "6") (pinfunction "6_6") (pintype "passive"))
    )
    (net (code "35") (name "/RC4") (class "Default")
      (node (ref "DIP1") (pin "15") (pinfunction "RC4/SDI/SDA_15") (pintype "bidirectional"))
      (node (ref "DIP2") (pin "23") (pinfunction "RC4/SDI/SDA_23") (pintype "bidirectional"))
      (node (ref "J11") (pin "23") (pinfunction "23_23") (pintype "passive"))
      (node (ref "J12") (pin "23") (pinfunction "23_23") (pintype "passive"))
      (node (ref "J13") (pin "23") (pinfunction "23_23") (pintype "passive"))
      (node (ref "J2") (pin "2") (pinfunction "D-_2") (pintype "input"))
      (node (ref "J6") (pin "5") (pinfunction "5_5") (pintype "passive"))
      (node (ref "SW11") (pin "2") (pinfunction "2_2") (pintype "passive"))
      (node (ref "SW12") (pin "2") (pinfunction "2_2") (pintype "passive"))
      (node (ref "SW13") (pin "2") (pinfunction "2_2") (pintype "passive"))
      (node (ref "SW14") (pin "2") (pinfunction "2_2") (pintype "passive"))
      (node (ref "SW4") (pin "7") (pinfunction "7_7") (pintype "passive"))
    )
    (net (code "36") (name "/RC5") (class "Default")
      (node (ref "DIP1") (pin "16") (pinfunction "RC5/SDO_16") (pintype "bidirectional"))
      (node (ref "DIP2") (pin "24") (pinfunction "RC5/SDO_24") (pintype "bidirectional"))
      (node (ref "J11") (pin "24") (pinfunction "24_24") (pintype "passive"))
      (node (ref "J12") (pin "24") (pinfunction "24_24") (pintype "passive"))
      (node (ref "J13") (pin "24") (pinfunction "24_24") (pintype "passive"))
      (node (ref "J2") (pin "3") (pinfunction "D+_3") (pintype "input"))
      (node (ref "J6") (pin "6") (pinfunction "6_6") (pintype "passive"))
      (node (ref "SW15") (pin "2") (pinfunction "2_2") (pintype "passive"))
      (node (ref "SW16") (pin "2") (pinfunction "2_2") (pintype "passive"))
      (node (ref "SW17") (pin "2") (pinfunction "2_2") (pintype "passive"))
      (node (ref "SW18") (pin "2") (pinfunction "2_2") (pintype "passive"))
    )
    (net (code "37") (name "/RC6") (class "Default")
      (node (ref "DIP1") (pin "17") (pinfunction "RC6/TX/CK_17") (pintype "bidirectional"))
      (node (ref "DIP2") (pin "25") (pinfunction "RC6/TX/CK_25") (pintype "bidirectional"))
      (node (ref "J11") (pin "25") (pinfunction "25_25") (pintype "passive"))
      (node (ref "J12") (pin "25") (pinfunction "25_25") (pintype "passive"))
      (node (ref "J13") (pin "25") (pinfunction "25_25") (pintype "passive"))
      (node (ref "J6") (pin "7") (pinfunction "7_7") (pintype "passive"))
      (node (ref "R38") (pin "1") (pinfunction "1_1") (pintype "passive"))
      (node (ref "SW19") (pin "2") (pinfunction "2_2") (pintype "passive"))
      (node (ref "SW20") (pin "2") (pinfunction "2_2") (pintype "passive"))
      (node (ref "SW21") (pin "2") (pinfunction "2_2") (pintype "passive"))
      (node (ref "SW22") (pin "2") (pinfunction "2_2") (pintype "passive"))
      (node (ref "U7") (pin "11") (pinfunction "T1IN_11") (pintype "input"))
    )
    (net (code "38") (name "/RC7") (class "Default")
      (node (ref "DIP1") (pin "18") (pinfunction "RC7/RX/DT_18") (pintype "bidirectional"))
      (node (ref "DIP2") (pin "26") (pinfunction "RC7/RX/DT_26") (pintype "bidirectional"))
      (node (ref "J11") (pin "26") (pinfunction "26_26") (pintype "passive"))
      (node (ref "J12") (pin "26") (pinfunction "26_26") (pintype "passive"))
      (node (ref "J13") (pin "26") (pinfunction "26_26") (pintype "passive"))
      (node (ref "J6") (pin "8") (pinfunction "8_8") (pintype "passive"))
      (node (ref "SW23") (pin "2") (pinfunction "2_2") (pintype "passive"))
      (node (ref "SW24") (pin "2") (pinfunction "2_2") (pintype "passive"))
      (node (ref "SW25") (pin "2") (pinfunction "2_2") (pintype "passive"))
      (node (ref "SW26") (pin "2") (pinfunction "2_2") (pintype "passive"))
      (node (ref "U7") (pin "12") (pinfunction "R1OUT_12") (pintype "output"))
    )
    (net (code "39") (name "/RD0") (class "Default")
      (node (ref "DIP2") (pin "19") (pinfunction "RD0/PSP0_19") (pintype "bidirectional"))
      (node (ref "J11") (pin "27") (pinfunction "27_27") (pintype "passive"))
      (node (ref "J12") (pin "27") (pinfunction "27_27") (pintype "passive"))
      (node (ref "J13") (pin "27") (pinfunction "27_27") (pintype "passive"))
      (node (ref "J7") (pin "1") (pinfunction "1_1") (pintype "passive"))
    )
    (net (code "40") (name "/RD1") (class "Default")
      (node (ref "DIP2") (pin "20") (pinfunction "RD1/PSP1_20") (pintype "bidirectional"))
      (node (ref "J11") (pin "28") (pinfunction "28_28") (pintype "passive"))
      (node (ref "J12") (pin "28") (pinfunction "28_28") (pintype "passive"))
      (node (ref "J13") (pin "28") (pinfunction "28_28") (pintype "passive"))
      (node (ref "J7") (pin "2") (pinfunction "2_2") (pintype "passive"))
    )
    (net (code "41") (name "/RD2") (class "Default")
      (node (ref "DIP2") (pin "21") (pinfunction "RD2/PSP2_21") (pintype "bidirectional"))
      (node (ref "J11") (pin "29") (pinfunction "29_29") (pintype "passive"))
      (node (ref "J12") (pin "29") (pinfunction "29_29") (pintype "passive"))
      (node (ref "J13") (pin "29") (pinfunction "29_29") (pintype "passive"))
      (node (ref "J7") (pin "3") (pinfunction "3_3") (pintype "passive"))
    )
    (net (code "42") (name "/RD3") (class "Default")
      (node (ref "DIP2") (pin "22") (pinfunction "RD3/PSP3_22") (pintype "bidirectional"))
      (node (ref "J11") (pin "30") (pinfunction "30_30") (pintype "passive"))
      (node (ref "J12") (pin "30") (pinfunction "30_30") (pintype "passive"))
      (node (ref "J13") (pin "30") (pinfunction "30_30") (pintype "passive"))
      (node (ref "J7") (pin "4") (pinfunction "4_4") (pintype "passive"))
    )
    (net (code "43") (name "/RD4") (class "Default")
      (node (ref "DIP2") (pin "27") (pinfunction "RD4/PSP4_27") (pintype "bidirectional"))
      (node (ref "J11") (pin "31") (pinfunction "31_31") (pintype "passive"))
      (node (ref "J12") (pin "31") (pinfunction "31_31") (pintype "passive"))
      (node (ref "J13") (pin "31") (pinfunction "31_31") (pintype "passive"))
      (node (ref "J7") (pin "5") (pinfunction "5_5") (pintype "passive"))
    )
    (net (code "44") (name "/RD5") (class "Default")
      (node (ref "DIP2") (pin "28") (pinfunction "RD5/PSP5/P1B_28") (pintype "bidirectional"))
      (node (ref "J11") (pin "32") (pinfunction "32_32") (pintype "passive"))
      (node (ref "J12") (pin "32") (pinfunction "32_32") (pintype "passive"))
      (node (ref "J13") (pin "32") (pinfunction "32_32") (pintype "passive"))
      (node (ref "J7") (pin "6") (pinfunction "6_6") (pintype "passive"))
    )
    (net (code "45") (name "/RD6") (class "Default")
      (node (ref "DIP2") (pin "29") (pinfunction "RD6/PSP6/P1C_29") (pintype "bidirectional"))
      (node (ref "J11") (pin "33") (pinfunction "33_33") (pintype "passive"))
      (node (ref "J12") (pin "33") (pinfunction "33_33") (pintype "passive"))
      (node (ref "J13") (pin "33") (pinfunction "33_33") (pintype "passive"))
      (node (ref "J7") (pin "7") (pinfunction "7_7") (pintype "passive"))
    )
    (net (code "46") (name "/RD7") (class "Default")
      (node (ref "DIP2") (pin "30") (pinfunction "RD7/PSP7/P1D_30") (pintype "bidirectional"))
      (node (ref "J11") (pin "34") (pinfunction "34_34") (pintype "passive"))
      (node (ref "J12") (pin "34") (pinfunction "34_34") (pintype "passive"))
      (node (ref "J13") (pin "34") (pinfunction "34_34") (pintype "passive"))
      (node (ref "J7") (pin "8") (pinfunction "8_8") (pintype "passive"))
    )
    (net (code "47") (name "/RE0") (class "Default")
      (node (ref "DIP2") (pin "8") (pinfunction "RE0/~{RD}/AN5_8") (pintype "bidirectional"))
      (node (ref "J11") (pin "35") (pinfunction "35_35") (pintype "passive"))
      (node (ref "J12") (pin "35") (pinfunction "35_35") (pintype "passive"))
      (node (ref "J13") (pin "35") (pinfunction "35_35") (pintype "passive"))
      (node (ref "J8") (pin "1") (pinfunction "1_1") (pintype "passive"))
    )
    (net (code "48") (name "/RE1") (class "Default")
      (node (ref "DIP2") (pin "9") (pinfunction "RE1/~{WR}/AN6_9") (pintype "bidirectional"))
      (node (ref "J11") (pin "36") (pinfunction "36_36") (pintype "passive"))
      (node (ref "J12") (pin "36") (pinfunction "36_36") (pintype "passive"))
      (node (ref "J13") (pin "36") (pinfunction "36_36") (pintype "passive"))
      (node (ref "J8") (pin "2") (pinfunction "2_2") (pintype "passive"))
    )
    (net (code "49") (name "/RE2") (class "Default")
      (node (ref "DIP2") (pin "10") (pinfunction "RE2/~{CS}/AN7_10") (pintype "bidirectional"))
      (node (ref "J11") (pin "37") (pinfunction "37_37") (pintype "passive"))
      (node (ref "J12") (pin "37") (pinfunction "37_37") (pintype "passive"))
      (node (ref "J13") (pin "37") (pinfunction "37_37") (pintype "passive"))
      (node (ref "J8") (pin "3") (pinfunction "3_3") (pintype "passive"))
    )
    (net (code "50") (name "/RE3") (class "Default")
      (node (ref "DIP1") (pin "1") (pinfunction "~{MCLR}/VPP/RE3_1") (pintype "input"))
      (node (ref "DIP2") (pin "1") (pinfunction "~{MCLR}/VPP/RE3_1") (pintype "input"))
      (node (ref "J11") (pin "38") (pinfunction "38_38") (pintype "passive"))
      (node (ref "J12") (pin "38") (pinfunction "38_38") (pintype "passive"))
      (node (ref "J13") (pin "38") (pinfunction "38_38") (pintype "passive"))
      (node (ref "J21") (pin "1") (pinfunction "1_1") (pintype "passive"))
      (node (ref "J8") (pin "4") (pinfunction "4_4") (pintype "passive"))
      (node (ref "SW1") (pin "1") (pinfunction "1_1") (pintype "passive"))
      (node (ref "SW2") (pin "4") (pinfunction "4_4") (pintype "passive"))
    )
    (net (code "51") (name "/RTC_SCL") (class "Default")
      (node (ref "R48") (pin "1") (pinfunction "1_1") (pintype "passive"))
      (node (ref "SW4") (pin "3") (pinfunction "3_3") (pintype "passive"))
      (node (ref "U6") (pin "6") (pinfunction "SCL_6") (pintype "passive"))
    )
    (net (code "52") (name "/RTC_SDA") (class "Default")
      (node (ref "R49") (pin "1") (pinfunction "1_1") (pintype "passive"))
      (node (ref "SW4") (pin "2") (pinfunction "2_2") (pintype "passive"))
      (node (ref "U6") (pin "5") (pinfunction "SDA_5") (pintype "passive"))
    )
    (net (code "53") (name "/RxIN") (class "Default")
      (node (ref "P1") (pin "3") (pinfunction "3_3") (pintype "passive"))
      (node (ref "U7") (pin "13") (pinfunction "R1IN_13") (pintype "input"))
    )
    (net (code "54") (name "/TxOUT") (class "Default")
      (node (ref "P1") (pin "2") (pinfunction "2_2") (pintype "passive"))
      (node (ref "U7") (pin "14") (pinfunction "T1OUT_14") (pintype "output"))
    )
    (net (code "55") (name "/USB_D+") (class "Default")
      (node (ref "J3") (pin "3") (pinfunction "D+_3") (pintype "input"))
      (node (ref "U1") (pin "16") (pinfunction "RC5/D+/VP_16") (pintype "bidirectional"))
    )
    (net (code "56") (name "/USB_D-") (class "Default")
      (node (ref "J3") (pin "2") (pinfunction "D-_2") (pintype "input"))
      (node (ref "U1") (pin "15") (pinfunction "RC4/D-/VM_15") (pintype "bidirectional"))
    )
    (net (code "57") (name "/VDD_TGT_ADJ") (class "Default")
      (node (ref "R4") (pin "2") (pinfunction "2_2") (pintype "passive"))
      (node (ref "U1") (pin "13") (pinfunction "RC2/CCP1_13") (pintype "bidirectional"))
    )
    (net (code "58") (name "/VDD_TGT_FB") (class "Default")
      (node (ref "R26") (pin "2") (pinfunction "2_2") (pintype "passive"))
      (node (ref "U1") (pin "3") (pinfunction "RA1/AN1_3") (pintype "bidirectional"))
    )
    (net (code "59") (name "/VDD_TGT_N") (class "Default")
      (node (ref "R12") (pin "1") (pinfunction "1_1") (pintype "passive"))
      (node (ref "U1") (pin "24") (pinfunction "RB3/AN9/CCP2/VPO_24") (pintype "bidirectional"))
      (node (ref "U5") (pin "1") (pinfunction "G_1") (pintype "passive"))
    )
    (net (code "60") (name "/VDD_TGT_OUTPUT") (class "Default")
      (node (ref "D2") (pin "1") (pinfunction "A1_1") (pintype "passive"))
      (node (ref "D4") (pin "1") (pinfunction "K_1") (pintype "passive"))
      (node (ref "J22") (pin "2") (pinfunction "2_2") (pintype "passive"))
      (node (ref "R13") (pin "2") (pinfunction "2_2") (pintype "passive"))
      (node (ref "R26") (pin "1") (pinfunction "1_1") (pintype "passive"))
      (node (ref "SW2") (pin "6") (pinfunction "6_6") (pintype "passive"))
    )
    (net (code "61") (name "/VDD_TGT_P") (class "Default")
      (node (ref "D17") (pin "1") (pinfunction "1_1") (pintype "passive"))
      (node (ref "R16") (pin "1") (pinfunction "1_1") (pintype "passive"))
      (node (ref "R30") (pin "1") (pinfunction "1_1") (pintype "passive"))
      (node (ref "U1") (pin "25") (pinfunction "RB4/AN11/KBI0_25") (pintype "bidirectional"))
    )
    (net (code "62") (name "/VPP_FEEDBACK") (class "Default")
      (node (ref "R22") (pin "1") (pinfunction "1_1") (pintype "passive"))
      (node (ref "R24") (pin "2") (pinfunction "2_2") (pintype "passive"))
      (node (ref "U1") (pin "2") (pinfunction "RA0/AN0_2") (pintype "bidirectional"))
    )
    (net (code "63") (name "/VPP_ON") (class "Default")
      (node (ref "R27") (pin "1") (pinfunction "1_1") (pintype "passive"))
      (node (ref "U1") (pin "23") (pinfunction "RB2/AN8/INT2/VMO_23") (pintype "bidirectional"))
    )
    (net (code "64") (name "/VPP_OUTPUT") (class "Default")
      (node (ref "J22") (pin "1") (pinfunction "1_1") (pintype "passive"))
      (node (ref "Q6") (pin "3") (pinfunction "C_3") (pintype "passive"))
      (node (ref "R28") (pin "2") (pinfunction "2_2") (pintype "passive"))
      (node (ref "SW2") (pin "5") (pinfunction "5_5") (pintype "passive"))
    )
    (net (code "65") (name "/VPP_PUMP") (class "Default")
      (node (ref "R21") (pin "1") (pinfunction "1_1") (pintype "passive"))
      (node (ref "U1") (pin "12") (pinfunction "RC1/T1OSI/CCP2/~{UOE}_12") (pintype "bidirectional"))
    )
    (net (code "66") (name "/_SCL") (class "Default")
      (node (ref "R8") (pin "1") (pinfunction "1_1") (pintype "passive"))
      (node (ref "U1") (pin "22") (pinfunction "RB1/AN10/INT1/SCK/SCL_22") (pintype "bidirectional"))
    )
    (net (code "67") (name "/_SDA") (class "Default")
      (node (ref "R9") (pin "1") (pinfunction "1_1") (pintype "passive"))
      (node (ref "U1") (pin "21") (pinfunction "RB0/AN12/INT0/FLT0/SDI/SDA_21") (pintype "bidirectional"))
    )
    (net (code "68") (name "GND") (class "Default")
      (node (ref "BT1") (pin "2") (pinfunction "GND_2") (pintype "passive"))
      (node (ref "C1") (pin "2") (pinfunction "-_2") (pintype "passive"))
      (node (ref "C11") (pin "2") (pinfunction "2_2") (pintype "passive"))
      (node (ref "C12") (pin "2") (pinfunction "2_2") (pintype "passive"))
      (node (ref "C13") (pin "2") (pinfunction "2_2") (pintype "passive"))
      (node (ref "C14") (pin "2") (pinfunction "2_2") (pintype "passive"))
      (node (ref "C15") (pin "2") (pinfunction "2_2") (pintype "passive"))
      (node (ref "C17") (pin "2") (pinfunction "2_2") (pintype "passive"))
      (node (ref "C18") (pin "2") (pinfunction "2_2") (pintype "passive"))
      (node (ref "C19") (pin "2") (pinfunction "2_2") (pintype "passive"))
      (node (ref "C2") (pin "2") (pinfunction "2_2") (pintype "passive"))
      (node (ref "C20") (pin "2") (pinfunction "2_2") (pintype "passive"))
      (node (ref "C21") (pin "2") (pinfunction "2_2") (pintype "passive"))
      (node (ref "C22") (pin "2") (pinfunction "2_2") (pintype "passive"))
      (node (ref "C23") (pin "2") (pinfunction "2_2") (pintype "passive"))
      (node (ref "C24") (pin "2") (pinfunction "2_2") (pintype "passive"))
      (node (ref "C26") (pin "1") (pinfunction "1_1") (pintype "passive"))
      (node (ref "C27") (pin "2") (pinfunction "2_2") (pintype "passive"))
      (node (ref "C28") (pin "2") (pinfunction "2_2") (pintype "passive"))
      (node (ref "C3") (pin "2") (pinfunction "-_2") (pintype "passive"))
      (node (ref "C32") (pin "2") (pinfunction "2_2") (pintype "passive"))
      (node (ref "C33") (pin "2") (pinfunction "2_2") (pintype "passive"))
      (node (ref "C34") (pin "1") (pinfunction "1_1") (pintype "passive"))
      (node (ref "C4") (pin "2") (pinfunction "2_2") (pintype "passive"))
      (node (ref "C5") (pin "1") (pinfunction "1_1") (pintype "passive"))
      (node (ref "C6") (pin "1") (pinfunction "1_1") (pintype "passive"))
      (node (ref "C7") (pin "1") (pinfunction "1_1") (pintype "passive"))
      (node (ref "C8") (pin "1") (pinfunction "1_1") (pintype "passive"))
      (node (ref "D1") (pin "4") (pinfunction "-V_OUT_4") (pintype "passive"))
      (node (ref "D15") (pin "2") (pinfunction "2_2") (pintype "passive"))
      (node (ref "DIP1") (pin "19") (pinfunction "VSS_19") (pintype "power_in"))
      (node (ref "DIP1") (pin "8") (pinfunction "VSS_8") (pintype "power_in"))
      (node (ref "DIP2") (pin "12") (pinfunction "VSS_12") (pintype "power_in"))
      (node (ref "DIP2") (pin "31") (pinfunction "VSS_31") (pintype "power_in"))
      (node (ref "J11") (pin "19") (pinfunction "19_19") (pintype "passive"))
      (node (ref "J11") (pin "39") (pinfunction "39_39") (pintype "passive"))
      (node (ref "J12") (pin "19") (pinfunction "19_19") (pintype "passive"))
      (node (ref "J12") (pin "39") (pinfunction "39_39") (pintype "passive"))
      (node (ref "J13") (pin "19") (pinfunction "19_19") (pintype "passive"))
      (node (ref "J13") (pin "39") (pinfunction "39_39") (pintype "passive"))
      (node (ref "J14") (pin "3") (pinfunction "3_3") (pintype "passive"))
      (node (ref "J2") (pin "4") (pinfunction "GND_4") (pintype "power_in"))
      (node (ref "J21") (pin "3") (pinfunction "3_3") (pintype "passive"))
      (node (ref "J22") (pin "3") (pinfunction "3_3") (pintype "passive"))
      (node (ref "J3") (pin "4") (pinfunction "GND_4") (pintype "power_in"))
      (node (ref "J4") (pin "9") (pinfunction "9_9") (pintype "passive"))
      (node (ref "J5") (pin "9") (pinfunction "9_9") (pintype "passive"))
      (node (ref "J6") (pin "9") (pinfunction "9_9") (pintype "passive"))
      (node (ref "J7") (pin "9") (pinfunction "9_9") (pintype "passive"))
      (node (ref "J8") (pin "9") (pinfunction "9_9") (pintype "passive"))
      (node (ref "LCD1") (pin "1") (pinfunction "VSS_1") (pintype "passive"))
      (node (ref "LCD1") (pin "16") (pinfunction "LED-_16") (pintype "passive"))
      (node (ref "LCD1") (pin "5") (pinfunction "RD_5") (pintype "passive"))
      (node (ref "P1") (pin "5") (pinfunction "5_5") (pintype "passive"))
      (node (ref "Q2") (pin "3") (pinfunction "C_3") (pintype "passive"))
      (node (ref "Q3") (pin "3") (pinfunction "C_3") (pintype "passive"))
      (node (ref "Q4") (pin "2") (pinfunction "E_2") (pintype "passive"))
      (node (ref "Q5") (pin "3") (pinfunction "C_3") (pintype "passive"))
      (node (ref "Q7") (pin "2") (pinfunction "E_2") (pintype "passive"))
      (node (ref "Q8") (pin "2") (pinfunction "E_2") (pintype "passive"))
      (node (ref "R12") (pin "2") (pinfunction "2_2") (pintype "passive"))
      (node (ref "R17") (pin "1") (pinfunction "1_1") (pintype "passive"))
      (node (ref "R24") (pin "1") (pinfunction "1_1") (pintype "passive"))
      (node (ref "R3") (pin "2") (pinfunction "2_2") (pintype "passive"))
      (node (ref "R34") (pin "1") (pinfunction "1_1") (pintype "passive"))
      (node (ref "R35") (pin "1") (pinfunction "1_1") (pintype "passive"))
      (node (ref "R36") (pin "1") (pinfunction "1_1") (pintype "passive"))
      (node (ref "R37") (pin "1") (pinfunction "1_1") (pintype "passive"))
      (node (ref "R43") (pin "1") (pinfunction "1_1") (pintype "passive"))
      (node (ref "R52") (pin "3") (pinfunction "3_3") (pintype "passive"))
      (node (ref "R54") (pin "1") (pinfunction "1_1") (pintype "passive"))
      (node (ref "R6") (pin "2") (pinfunction "2_2") (pintype "passive"))
      (node (ref "R7") (pin "1") (pinfunction "1_1") (pintype "passive"))
      (node (ref "REG1") (pin "2") (pinfunction "GND_2") (pintype "passive"))
      (node (ref "SW1") (pin "7") (pinfunction "7_7") (pintype "passive"))
      (node (ref "SW6") (pin "1") (pinfunction "1_1") (pintype "passive"))
      (node (ref "U1") (pin "8") (pinfunction "VSS_8") (pintype "power_in"))
      (node (ref "U2") (pin "4") (pinfunction "-V_4") (pintype "passive"))
      (node (ref "U5") (pin "5") (pinfunction "S_5") (pintype "passive"))
      (node (ref "U6") (pin "4") (pinfunction "GND_4") (pintype "passive"))
      (node (ref "U7") (pin "15") (pinfunction "GND_15") (pintype "passive"))
    )
    (net (code "69") (name "Net-(BT1-+3V)") (class "Default")
      (node (ref "BT1") (pin "1") (pinfunction "+3V_1") (pintype "passive"))
      (node (ref "U6") (pin "3") (pinfunction "VBAT_3") (pintype "passive"))
    )
    (net (code "70") (name "Net-(C1-+)") (class "Default")
      (node (ref "C1") (pin "1") (pinfunction "+_1") (pintype "passive"))
      (node (ref "D1") (pin "1") (pinfunction "+V_OUT_1") (pintype "passive"))
      (node (ref "REG1") (pin "1") (pinfunction "Vin_1") (pintype "power_in"))
    )
    (net (code "71") (name "Net-(C26-Pad2)") (class "Default")
      (node (ref "C26") (pin "2") (pinfunction "2_2") (pintype "passive"))
      (node (ref "C6") (pin "2") (pinfunction "2_2") (pintype "passive"))
      (node (ref "SW1") (pin "3") (pinfunction "3_3") (pintype "passive"))
      (node (ref "Y1") (pin "2") (pinfunction "2_2") (pintype "passive"))
    )
    (net (code "72") (name "Net-(C27-Pad1)") (class "Default")
      (node (ref "C27") (pin "1") (pinfunction "1_1") (pintype "passive"))
      (node (ref "C28") (pin "1") (pinfunction "1_1") (pintype "passive"))
      (node (ref "SW3") (pin "4") (pinfunction "4_4") (pintype "passive"))
    )
    (net (code "73") (name "Net-(C34-Pad2)") (class "Default")
      (node (ref "C34") (pin "2") (pinfunction "2_2") (pintype "passive"))
      (node (ref "C5") (pin "2") (pinfunction "2_2") (pintype "passive"))
      (node (ref "SW1") (pin "4") (pinfunction "4_4") (pintype "passive"))
      (node (ref "Y1") (pin "1") (pinfunction "1_1") (pintype "passive"))
    )
    (net (code "74") (name "Net-(D1-AC1)") (class "Default")
      (node (ref "D1") (pin "2") (pinfunction "AC1_2") (pintype "passive"))
      (node (ref "J1") (pin "1") (pinfunction "T_1") (pintype "passive"))
    )
    (net (code "75") (name "Net-(D1-AC2)") (class "Default")
      (node (ref "D1") (pin "3") (pinfunction "AC2_3") (pintype "passive"))
      (node (ref "J1") (pin "2") (pinfunction "TN_2") (pintype "passive"))
      (node (ref "J1") (pin "3") (pinfunction "S_3") (pintype "power_in"))
    )
    (net (code "76") (name "Net-(D3-A)") (class "Default")
      (node (ref "D3") (pin "1") (pinfunction "A_1") (pintype "passive"))
      (node (ref "L1") (pin "2") (pinfunction "2_2") (pintype "passive"))
      (node (ref "Q4") (pin "3") (pinfunction "C_3") (pintype "passive"))
    )
    (net (code "77") (name "Net-(D3-K)") (class "Default")
      (node (ref "C22") (pin "1") (pinfunction "1_1") (pintype "passive"))
      (node (ref "D3") (pin "3") (pinfunction "K_3") (pintype "passive"))
      (node (ref "Q6") (pin "2") (pinfunction "E_2") (pintype "passive"))
      (node (ref "R22") (pin "2") (pinfunction "2_2") (pintype "passive"))
      (node (ref "R23") (pin "2") (pinfunction "2_2") (pintype "passive"))
    )
    (net (code "78") (name "Net-(D4-A)") (class "Default")
      (node (ref "D4") (pin "3") (pinfunction "A_3") (pintype "passive"))
      (node (ref "U5") (pin "4") (pinfunction "D_4") (pintype "passive"))
    )
    (net (code "79") (name "Net-(D6-Pad2)") (class "Default")
      (node (ref "D6") (pin "2") (pinfunction "2_2") (pintype "passive"))
      (node (ref "R44") (pin "2") (pinfunction "2_2") (pintype "passive"))
    )
    (net (code "80") (name "Net-(D7-Pad2)") (class "Default")
      (node (ref "D7") (pin "2") (pinfunction "2_2") (pintype "passive"))
      (node (ref "R44") (pin "3") (pinfunction "3_3") (pintype "passive"))
    )
    (net (code "81") (name "Net-(D8-Pad2)") (class "Default")
      (node (ref "D8") (pin "2") (pinfunction "2_2") (pintype "passive"))
      (node (ref "R44") (pin "4") (pinfunction "4_4") (pintype "passive"))
    )
    (net (code "82") (name "Net-(D9-Pad2)") (class "Default")
      (node (ref "D9") (pin "2") (pinfunction "2_2") (pintype "passive"))
      (node (ref "R44") (pin "5") (pinfunction "5_5") (pintype "passive"))
    )
    (net (code "83") (name "Net-(D10-Pad2)") (class "Default")
      (node (ref "D10") (pin "2") (pinfunction "2_2") (pintype "passive"))
      (node (ref "R44") (pin "6") (pinfunction "6_6") (pintype "passive"))
    )
    (net (code "84") (name "Net-(D11-Pad2)") (class "Default")
      (node (ref "D11") (pin "2") (pinfunction "2_2") (pintype "passive"))
      (node (ref "R44") (pin "7") (pinfunction "7_7") (pintype "passive"))
    )
    (net (code "85") (name "Net-(D12-Pad2)") (class "Default")
      (node (ref "D12") (pin "2") (pinfunction "2_2") (pintype "passive"))
      (node (ref "R44") (pin "8") (pinfunction "8_8") (pintype "passive"))
    )
    (net (code "86") (name "Net-(D13-Pad2)") (class "Default")
      (node (ref "D13") (pin "2") (pinfunction "2_2") (pintype "passive"))
      (node (ref "R44") (pin "9") (pinfunction "9_9") (pintype "passive"))
    )
    (net (code "87") (name "Net-(D14-A)") (class "Default")
      (node (ref "D14") (pin "1") (pinfunction "A_1") (pintype "passive"))
      (node (ref "P10") (pin "2") (pinfunction "2_2") (pintype "passive"))
      (node (ref "Q9") (pin "2") (pinfunction "C_2") (pintype "passive"))
    )
    (net (code "88") (name "Net-(D15-Pad1)") (class "Default")
      (node (ref "D15") (pin "1") (pinfunction "1_1") (pintype "passive"))
      (node (ref "R1") (pin "1") (pinfunction "1_1") (pintype "passive"))
    )
    (net (code "89") (name "Net-(D16-Pad2)") (class "Default")
      (node (ref "D16") (pin "2") (pinfunction "2_2") (pintype "passive"))
      (node (ref "R3") (pin "1") (pinfunction "1_1") (pintype "passive"))
    )
    (net (code "90") (name "Net-(D17-Pad2)") (class "Default")
      (node (ref "D17") (pin "2") (pinfunction "2_2") (pintype "passive"))
      (node (ref "R2") (pin "1") (pinfunction "1_1") (pintype "passive"))
    )
    (net (code "91") (name "Net-(J3-VBUS)") (class "Default")
      (node (ref "J3") (pin "1") (pinfunction "VBUS_1") (pintype "power_in"))
      (node (ref "REG1") (pin "3") (pinfunction "Vout_3") (pintype "passive"))
      (node (ref "SW5") (pin "1") (pinfunction "1_1") (pintype "passive"))
      (node (ref "SW5") (pin "4") (pinfunction "4_4") (pintype "passive"))
    )
    (net (code "92") (name "Net-(J17-Pad2)") (class "Default")
      (node (ref "J17") (pin "2") (pinfunction "2_2") (pintype "passive"))
      (node (ref "R55") (pin "2") (pinfunction "2_2") (pintype "passive"))
    )
    (net (code "93") (name "Net-(J18-Pad2)") (class "Default")
      (node (ref "J18") (pin "2") (pinfunction "2_2") (pintype "passive"))
      (node (ref "R56") (pin "2") (pinfunction "2_2") (pintype "passive"))
    )
    (net (code "94") (name "Net-(J19-Pad2)") (class "Default")
      (node (ref "J19") (pin "2") (pinfunction "2_2") (pintype "passive"))
      (node (ref "R57") (pin "2") (pinfunction "2_2") (pintype "passive"))
    )
    (net (code "95") (name "Net-(J20-Pad2)") (class "Default")
      (node (ref "J20") (pin "2") (pinfunction "2_2") (pintype "passive"))
      (node (ref "R58") (pin "2") (pinfunction "2_2") (pintype "passive"))
    )
    (net (code "96") (name "Net-(LCD1-LED+)") (class "Default")
      (node (ref "LCD1") (pin "15") (pinfunction "LED+_15") (pintype "passive"))
      (node (ref "R18") (pin "2") (pinfunction "2_2") (pintype "passive"))
    )
    (net (code "97") (name "Net-(LCD1-VCON)") (class "Default")
      (node (ref "LCD1") (pin "3") (pinfunction "VCON_3") (pintype "passive"))
      (node (ref "R52") (pin "2") (pinfunction "2_2") (pintype "passive"))
    )
    (net (code "98") (name "Net-(P1-Pad1)") (class "Default")
      (node (ref "P1") (pin "1") (pinfunction "1_1") (pintype "passive"))
      (node (ref "P1") (pin "4") (pinfunction "4_4") (pintype "passive"))
      (node (ref "P1") (pin "6") (pinfunction "6_6") (pintype "passive"))
    )
    (net (code "99") (name "Net-(Q1-G)") (class "Default")
      (node (ref "Q1") (pin "1") (pinfunction "G_1") (pintype "passive"))
      (node (ref "R31") (pin "2") (pinfunction "2_2") (pintype "passive"))
    )
    (net (code "100") (name "Net-(Q2-E)") (class "Default")
      (node (ref "Q2") (pin "2") (pinfunction "E_2") (pintype "passive"))
      (node (ref "R10") (pin "2") (pinfunction "2_2") (pintype "passive"))
      (node (ref "R11") (pin "1") (pinfunction "1_1") (pintype "passive"))
    )
    (net (code "101") (name "Net-(Q3-E)") (class "Default")
      (node (ref "Q3") (pin "2") (pinfunction "E_2") (pintype "passive"))
      (node (ref "R14") (pin "2") (pinfunction "2_2") (pintype "passive"))
      (node (ref "R15") (pin "1") (pinfunction "1_1") (pintype "passive"))
    )
    (net (code "102") (name "Net-(Q4-B)") (class "Default")
      (node (ref "Q4") (pin "1") (pinfunction "B_1") (pintype "passive"))
      (node (ref "R21") (pin "2") (pinfunction "2_2") (pintype "passive"))
    )
    (net (code "103") (name "Net-(Q5-E)") (class "Default")
      (node (ref "Q5") (pin "2") (pinfunction "E_2") (pintype "passive"))
      (node (ref "R19") (pin "2") (pinfunction "2_2") (pintype "passive"))
      (node (ref "R20") (pin "1") (pinfunction "1_1") (pintype "passive"))
    )
    (net (code "104") (name "Net-(Q6-B)") (class "Default")
      (node (ref "Q6") (pin "1") (pinfunction "B_1") (pintype "passive"))
      (node (ref "R23") (pin "1") (pinfunction "1_1") (pintype "passive"))
      (node (ref "R25") (pin "2") (pinfunction "2_2") (pintype "passive"))
    )
    (net (code "105") (name "Net-(Q7-B)") (class "Default")
      (node (ref "Q7") (pin "1") (pinfunction "B_1") (pintype "passive"))
      (node (ref "R27") (pin "2") (pinfunction "2_2") (pintype "passive"))
    )
    (net (code "106") (name "Net-(Q7-C)") (class "Default")
      (node (ref "Q7") (pin "3") (pinfunction "C_3") (pintype "passive"))
      (node (ref "R25") (pin "1") (pinfunction "1_1") (pintype "passive"))
    )
    (net (code "107") (name "Net-(Q8-B)") (class "Default")
      (node (ref "Q8") (pin "1") (pinfunction "B_1") (pintype "passive"))
      (node (ref "R29") (pin "2") (pinfunction "2_2") (pintype "passive"))
    )
    (net (code "108") (name "Net-(Q8-C)") (class "Default")
      (node (ref "Q8") (pin "3") (pinfunction "C_3") (pintype "passive"))
      (node (ref "R28") (pin "1") (pinfunction "1_1") (pintype "passive"))
    )
    (net (code "109") (name "Net-(Q9-B)") (class "Default")
      (node (ref "Q9") (pin "3") (pinfunction "B_3") (pintype "passive"))
      (node (ref "R47") (pin "2") (pinfunction "2_2") (pintype "passive"))
    )
    (net (code "110") (name "Net-(Q9-E)") (class "Default")
      (node (ref "Q9") (pin "1") (pinfunction "E_1") (pintype "passive"))
      (node (ref "R43") (pin "2") (pinfunction "2_2") (pintype "passive"))
    )
    (net (code "111") (name "Net-(R13-Pad1)") (class "Default")
      (node (ref "R13") (pin "1") (pinfunction "1_1") (pintype "passive"))
      (node (ref "U5") (pin "6") (pinfunction "D_6") (pintype "passive"))
    )
    (net (code "112") (name "Net-(R30-Pad2)") (class "Default")
      (node (ref "R30") (pin "2") (pinfunction "2_2") (pintype "passive"))
      (node (ref "U5") (pin "3") (pinfunction "G_3") (pintype "passive"))
    )
    (net (code "113") (name "Net-(R53-Pad2)") (class "Default")
      (node (ref "R53") (pin "2") (pinfunction "2_2") (pintype "passive"))
      (node (ref "R54") (pin "2") (pinfunction "2_2") (pintype "passive"))
    )
    (net (code "114") (name "Net-(U1-OSC1{slash}CLKI)") (class "Default")
      (node (ref "C8") (pin "2") (pinfunction "2_2") (pintype "passive"))
      (node (ref "U1") (pin "9") (pinfunction "OSC1/CLKI_9") (pintype "input"))
      (node (ref "Y2") (pin "2") (pinfunction "2_2") (pintype "passive"))
    )
    (net (code "115") (name "Net-(U1-OSC2{slash}CLKO{slash}RA6)") (class "Default")
      (node (ref "C7") (pin "2") (pinfunction "2_2") (pintype "passive"))
      (node (ref "U1") (pin "10") (pinfunction "OSC2/CLKO/RA6_10") (pintype "bidirectional"))
      (node (ref "Y2") (pin "1") (pinfunction "1_1") (pintype "passive"))
    )
    (net (code "116") (name "Net-(U1-VUSB)") (class "Default")
      (node (ref "C15") (pin "1") (pinfunction "1_1") (pintype "passive"))
      (node (ref "U1") (pin "14") (pinfunction "VUSB_14") (pintype "output"))
    )
    (net (code "117") (name "Net-(U2A-IN+)") (class "Default")
      (node (ref "R5") (pin "1") (pinfunction "1_1") (pintype "passive"))
      (node (ref "R6") (pin "1") (pinfunction "1_1") (pintype "passive"))
      (node (ref "U2") (pin "3") (pinfunction "IN+_3") (pintype "input"))
    )
    (net (code "118") (name "Net-(U2A-IN-)") (class "Default")
      (node (ref "C18") (pin "1") (pinfunction "1_1") (pintype "passive"))
      (node (ref "R4") (pin "1") (pinfunction "1_1") (pintype "passive"))
      (node (ref "U2") (pin "2") (pinfunction "IN-_2") (pintype "input"))
    )
    (net (code "119") (name "Net-(U2A-OUT)") (class "Default")
      (node (ref "R31") (pin "1") (pinfunction "1_1") (pintype "passive"))
      (node (ref "U2") (pin "1") (pinfunction "OUT_1") (pintype "output"))
    )
    (net (code "120") (name "Net-(U6-X1)") (class "Default")
      (node (ref "U6") (pin "1") (pinfunction "X1_1") (pintype "passive"))
      (node (ref "Y3") (pin "2") (pinfunction "2_2") (pintype "passive"))
    )
    (net (code "121") (name "Net-(U6-X2)") (class "Default")
      (node (ref "U6") (pin "2") (pinfunction "X2_2") (pintype "passive"))
      (node (ref "Y3") (pin "1") (pinfunction "1_1") (pintype "passive"))
    )
    (net (code "122") (name "Net-(U7-C1+)") (class "Default")
      (node (ref "C30") (pin "1") (pinfunction "1_1") (pintype "passive"))
      (node (ref "U7") (pin "1") (pinfunction "C1+_1") (pintype "passive"))
    )
    (net (code "123") (name "Net-(U7-C1-)") (class "Default")
      (node (ref "C30") (pin "2") (pinfunction "2_2") (pintype "passive"))
      (node (ref "U7") (pin "3") (pinfunction "C1-_3") (pintype "passive"))
    )
    (net (code "124") (name "Net-(U7-C2+)") (class "Default")
      (node (ref "C31") (pin "1") (pinfunction "1_1") (pintype "passive"))
      (node (ref "U7") (pin "4") (pinfunction "C2+_4") (pintype "passive"))
    )
    (net (code "125") (name "Net-(U7-C2-)") (class "Default")
      (node (ref "C31") (pin "2") (pinfunction "2_2") (pintype "passive"))
      (node (ref "U7") (pin "5") (pinfunction "C2-_5") (pintype "passive"))
    )
    (net (code "126") (name "Net-(U7-VS+)") (class "Default")
      (node (ref "C29") (pin "2") (pinfunction "2_2") (pintype "passive"))
      (node (ref "U7") (pin "2") (pinfunction "VS+_2") (pintype "power_in"))
    )
    (net (code "127") (name "Net-(U7-VS-)") (class "Default")
      (node (ref "C32") (pin "1") (pinfunction "1_1") (pintype "passive"))
      (node (ref "U7") (pin "6") (pinfunction "VS-_6") (pintype "power_in"))
    )
    (net (code "128") (name "VCC") (class "Default")
      (node (ref "C17") (pin "1") (pinfunction "1_1") (pintype "passive"))
      (node (ref "C19") (pin "1") (pinfunction "1_1") (pintype "passive"))
      (node (ref "C2") (pin "1") (pinfunction "1_1") (pintype "passive"))
      (node (ref "C20") (pin "1") (pinfunction "1_1") (pintype "passive"))
      (node (ref "C21") (pin "1") (pinfunction "1_1") (pintype "passive"))
      (node (ref "C23") (pin "1") (pinfunction "1_1") (pintype "passive"))
      (node (ref "C24") (pin "1") (pinfunction "1_1") (pintype "passive"))
      (node (ref "C3") (pin "1") (pinfunction "+_1") (pintype "passive"))
      (node (ref "DIP1") (pin "20") (pinfunction "VDD_20") (pintype "power_in"))
      (node (ref "DIP2") (pin "11") (pinfunction "VDD_11") (pintype "power_in"))
      (node (ref "DIP2") (pin "32") (pinfunction "VDD_32") (pintype "power_in"))
      (node (ref "J11") (pin "20") (pinfunction "20_20") (pintype "passive"))
      (node (ref "J11") (pin "40") (pinfunction "40_40") (pintype "passive"))
      (node (ref "J12") (pin "20") (pinfunction "20_20") (pintype "passive"))
      (node (ref "J12") (pin "40") (pinfunction "40_40") (pintype "passive"))
      (node (ref "J13") (pin "20") (pinfunction "20_20") (pintype "passive"))
      (node (ref "J13") (pin "40") (pinfunction "40_40") (pintype "passive"))
      (node (ref "J14") (pin "4") (pinfunction "4_4") (pintype "passive"))
      (node (ref "J17") (pin "1") (pinfunction "1_1") (pintype "passive"))
      (node (ref "J18") (pin "1") (pinfunction "1_1") (pintype "passive"))
      (node (ref "J19") (pin "1") (pinfunction "1_1") (pintype "passive"))
      (node (ref "J2") (pin "1") (pinfunction "VBUS_1") (pintype "power_in"))
      (node (ref "J20") (pin "1") (pinfunction "1_1") (pintype "passive"))
      (node (ref "J21") (pin "2") (pinfunction "2_2") (pintype "passive"))
      (node (ref "J4") (pin "10") (pinfunction "10_10") (pintype "passive"))
      (node (ref "J5") (pin "10") (pinfunction "10_10") (pintype "passive"))
      (node (ref "J6") (pin "10") (pinfunction "10_10") (pintype "passive"))
      (node (ref "J7") (pin "10") (pinfunction "10_10") (pintype "passive"))
      (node (ref "J8") (pin "10") (pinfunction "10_10") (pintype "passive"))
      (node (ref "Q1") (pin "2") (pinfunction "S_2") (pintype "passive"))
      (node (ref "R1") (pin "2") (pinfunction "2_2") (pintype "passive"))
      (node (ref "R16") (pin "2") (pinfunction "2_2") (pintype "passive"))
      (node (ref "R2") (pin "2") (pinfunction "2_2") (pintype "passive"))
      (node (ref "R32") (pin "2") (pinfunction "2_2") (pintype "passive"))
      (node (ref "R34") (pin "2") (pinfunction "2_2") (pintype "passive"))
      (node (ref "R48") (pin "2") (pinfunction "2_2") (pintype "passive"))
      (node (ref "R49") (pin "2") (pinfunction "2_2") (pintype "passive"))
      (node (ref "R51") (pin "2") (pinfunction "2_2") (pintype "passive"))
      (node (ref "R54") (pin "3") (pinfunction "3_3") (pintype "passive"))
      (node (ref "R8") (pin "2") (pinfunction "2_2") (pintype "passive"))
      (node (ref "R9") (pin "2") (pinfunction "2_2") (pintype "passive"))
      (node (ref "SW2") (pin "3") (pinfunction "3_3") (pintype "passive"))
      (node (ref "SW3") (pin "1") (pinfunction "1_1") (pintype "passive"))
      (node (ref "SW3") (pin "2") (pinfunction "2_2") (pintype "passive"))
      (node (ref "SW3") (pin "3") (pinfunction "3_3") (pintype "passive"))
      (node (ref "SW4") (pin "5") (pinfunction "5_5") (pintype "passive"))
      (node (ref "SW5") (pin "3") (pinfunction "3_3") (pintype "passive"))
      (node (ref "SW5") (pin "6") (pinfunction "6_6") (pintype "passive"))
      (node (ref "U1") (pin "20") (pinfunction "VDD_20") (pintype "power_in"))
      (node (ref "U2") (pin "8") (pinfunction "+V_8") (pintype "passive"))
      (node (ref "U6") (pin "8") (pinfunction "VCC_8") (pintype "passive"))
    )
    (net (code "129") (name "VCC_LCD") (class "Default")
      (node (ref "LCD1") (pin "2") (pinfunction "VDD_2") (pintype "passive"))
      (node (ref "R18") (pin "1") (pinfunction "1_1") (pintype "passive"))
      (node (ref "R52") (pin "1") (pinfunction "1_1") (pintype "passive"))
      (node (ref "SW3") (pin "8") (pinfunction "8_8") (pintype "passive"))
    )
    (net (code "130") (name "VCC_MOTOR") (class "Default")
      (node (ref "C4") (pin "1") (pinfunction "1_1") (pintype "passive"))
      (node (ref "D14") (pin "2") (pinfunction "K_2") (pintype "passive"))
      (node (ref "P10") (pin "1") (pinfunction "1_1") (pintype "passive"))
      (node (ref "SW4") (pin "4") (pinfunction "4_4") (pintype "passive"))
    )
    (net (code "131") (name "VCC_PS2") (class "Default")
      (node (ref "R40") (pin "2") (pinfunction "2_2") (pintype "passive"))
      (node (ref "R41") (pin "2") (pinfunction "2_2") (pintype "passive"))
      (node (ref "SW3") (pin "6") (pinfunction "6_6") (pintype "passive"))
    )
    (net (code "132") (name "VCC_UART") (class "Default")
      (node (ref "C29") (pin "1") (pinfunction "1_1") (pintype "passive"))
      (node (ref "R38") (pin "2") (pinfunction "2_2") (pintype "passive"))
      (node (ref "SW3") (pin "7") (pinfunction "7_7") (pintype "passive"))
      (node (ref "U7") (pin "16") (pinfunction "VCC_16") (pintype "power_in"))
    )
    (net (code "133") (name "unconnected-(D2-A2-Pad2)") (class "Default")
      (node (ref "D2") (pin "2") (pinfunction "A2_2") (pintype "passive"))
    )
    (net (code "134") (name "unconnected-(J2-SHLD-Pad5)") (class "Default")
      (node (ref "J2") (pin "5") (pinfunction "SHLD_5") (pintype "passive+no_connect"))
    )
    (net (code "135") (name "unconnected-(J2-SHLD-Pad6)") (class "Default")
      (node (ref "J2") (pin "6") (pinfunction "SHLD_6") (pintype "passive+no_connect"))
    )
    (net (code "136") (name "unconnected-(J3-SHLD-Pad5)") (class "Default")
      (node (ref "J3") (pin "5") (pinfunction "SHLD_5") (pintype "passive+no_connect"))
    )
    (net (code "137") (name "unconnected-(J3-SHLD-Pad6)") (class "Default")
      (node (ref "J3") (pin "6") (pinfunction "SHLD_6") (pintype "passive+no_connect"))
    )
    (net (code "138") (name "unconnected-(J8-Pad5)") (class "Default")
      (node (ref "J8") (pin "5") (pinfunction "5_5") (pintype "passive"))
    )
    (net (code "139") (name "unconnected-(J8-Pad6)") (class "Default")
      (node (ref "J8") (pin "6") (pinfunction "6_6") (pintype "passive"))
    )
    (net (code "140") (name "unconnected-(J8-Pad7)") (class "Default")
      (node (ref "J8") (pin "7") (pinfunction "7_7") (pintype "passive"))
    )
    (net (code "141") (name "unconnected-(J8-Pad8)") (class "Default")
      (node (ref "J8") (pin "8") (pinfunction "8_8") (pintype "passive"))
    )
    (net (code "142") (name "unconnected-(J14-Pad2)") (class "Default")
      (node (ref "J14") (pin "2") (pinfunction "2_2") (pintype "passive+no_connect"))
    )
    (net (code "143") (name "unconnected-(J14-Pad6)") (class "Default")
      (node (ref "J14") (pin "6") (pinfunction "6_6") (pintype "passive+no_connect"))
    )
    (net (code "144") (name "unconnected-(J14-PadS)") (class "Default")
      (node (ref "J14") (pin "S") (pinfunction "S_S") (pintype "input+no_connect"))
    )
    (net (code "145") (name "unconnected-(J17-Pad3)") (class "Default")
      (node (ref "J17") (pin "3") (pinfunction "3_3") (pintype "passive"))
    )
    (net (code "146") (name "unconnected-(J18-Pad3)") (class "Default")
      (node (ref "J18") (pin "3") (pinfunction "3_3") (pintype "passive"))
    )
    (net (code "147") (name "unconnected-(J19-Pad3)") (class "Default")
      (node (ref "J19") (pin "3") (pinfunction "3_3") (pintype "passive"))
    )
    (net (code "148") (name "unconnected-(J20-Pad3)") (class "Default")
      (node (ref "J20") (pin "3") (pinfunction "3_3") (pintype "passive"))
    )
    (net (code "149") (name "unconnected-(J21-Pad6)") (class "Default")
      (node (ref "J21") (pin "6") (pinfunction "6_6") (pintype "passive+no_connect"))
    )
    (net (code "150") (name "unconnected-(LCD1-D0-Pad7)") (class "Default")
      (node (ref "LCD1") (pin "7") (pinfunction "D0_7") (pintype "passive"))
    )
    (net (code "151") (name "unconnected-(LCD1-D1-Pad8)") (class "Default")
      (node (ref "LCD1") (pin "8") (pinfunction "D1_8") (pintype "passive"))
    )
    (net (code "152") (name "unconnected-(LCD1-D2-Pad9)") (class "Default")
      (node (ref "LCD1") (pin "9") (pinfunction "D2_9") (pintype "passive"))
    )
    (net (code "153") (name "unconnected-(LCD1-D3-Pad10)") (class "Default")
      (node (ref "LCD1") (pin "10") (pinfunction "D3_10") (pintype "passive"))
    )
    (net (code "154") (name "unconnected-(P1-Pad7)") (class "Default")
      (node (ref "P1") (pin "7") (pinfunction "7_7") (pintype "passive+no_connect"))
    )
    (net (code "155") (name "unconnected-(P1-Pad8)") (class "Default")
      (node (ref "P1") (pin "8") (pinfunction "8_8") (pintype "passive+no_connect"))
    )
    (net (code "156") (name "unconnected-(P1-Pad9)") (class "Default")
      (node (ref "P1") (pin "9") (pinfunction "9_9") (pintype "passive+no_connect"))
    )
    (net (code "157") (name "unconnected-(SW5-Pad2)") (class "Default")
      (node (ref "SW5") (pin "2") (pinfunction "2_2") (pintype "passive+no_connect"))
    )
    (net (code "158") (name "unconnected-(SW5-Pad5)") (class "Default")
      (node (ref "SW5") (pin "5") (pinfunction "5_5") (pintype "passive+no_connect"))
    )
    (net (code "159") (name "unconnected-(U1-RB6{slash}KBI2{slash}PGC-Pad27)") (class "Default")
      (node (ref "U1") (pin "27") (pinfunction "RB6/KBI2/PGC_27") (pintype "bidirectional+no_connect"))
    )
    (net (code "160") (name "unconnected-(U1-RB7{slash}KBI3{slash}PGD-Pad28)") (class "Default")
      (node (ref "U1") (pin "28") (pinfunction "RB7/KBI3/PGD_28") (pintype "bidirectional+no_connect"))
    )
    (net (code "161") (name "unconnected-(U1-RC6{slash}TX{slash}CK-Pad17)") (class "Default")
      (node (ref "U1") (pin "17") (pinfunction "RC6/TX/CK_17") (pintype "bidirectional+no_connect"))
    )
    (net (code "162") (name "unconnected-(U1-RC7{slash}RX{slash}DT{slash}SDO-Pad18)") (class "Default")
      (node (ref "U1") (pin "18") (pinfunction "RC7/RX/DT/SDO_18") (pintype "bidirectional+no_connect"))
    )
    (net (code "163") (name "unconnected-(U1-VSS-Pad19)") (class "Default")
      (node (ref "U1") (pin "19") (pinfunction "VSS_19") (pintype "power_in"))
    )
    (net (code "164") (name "unconnected-(U1-~{MCLR}{slash}VPP{slash}RE3-Pad1)") (class "Default")
      (node (ref "U1") (pin "1") (pinfunction "~{MCLR}/VPP/RE3_1") (pintype "input+no_connect"))
    )
    (net (code "165") (name "unconnected-(U6-OUT-Pad7)") (class "Default")
      (node (ref "U6") (pin "7") (pinfunction "OUT_7") (pintype "passive+no_connect"))
    )
    (net (code "166") (name "unconnected-(U7-R2IN-Pad8)") (class "Default")
      (node (ref "U7") (pin "8") (pinfunction "R2IN_8") (pintype "input+no_connect"))
    )
    (net (code "167") (name "unconnected-(U7-R2OUT-Pad9)") (class "Default")
      (node (ref "U7") (pin "9") (pinfunction "R2OUT_9") (pintype "output+no_connect"))
    )
    (net (code "168") (name "unconnected-(U7-T2IN-Pad10)") (class "Default")
      (node (ref "U7") (pin "10") (pinfunction "T2IN_10") (pintype "input+no_connect"))
    )
    (net (code "169") (name "unconnected-(U7-T2OUT-Pad7)") (class "Default")
      (node (ref "U7") (pin "7") (pinfunction "T2OUT_7") (pintype "output+no_connect"))
    )
  )
)
